# harp_expander.net
KiCad netlist of a schematic drawn in EAGLE
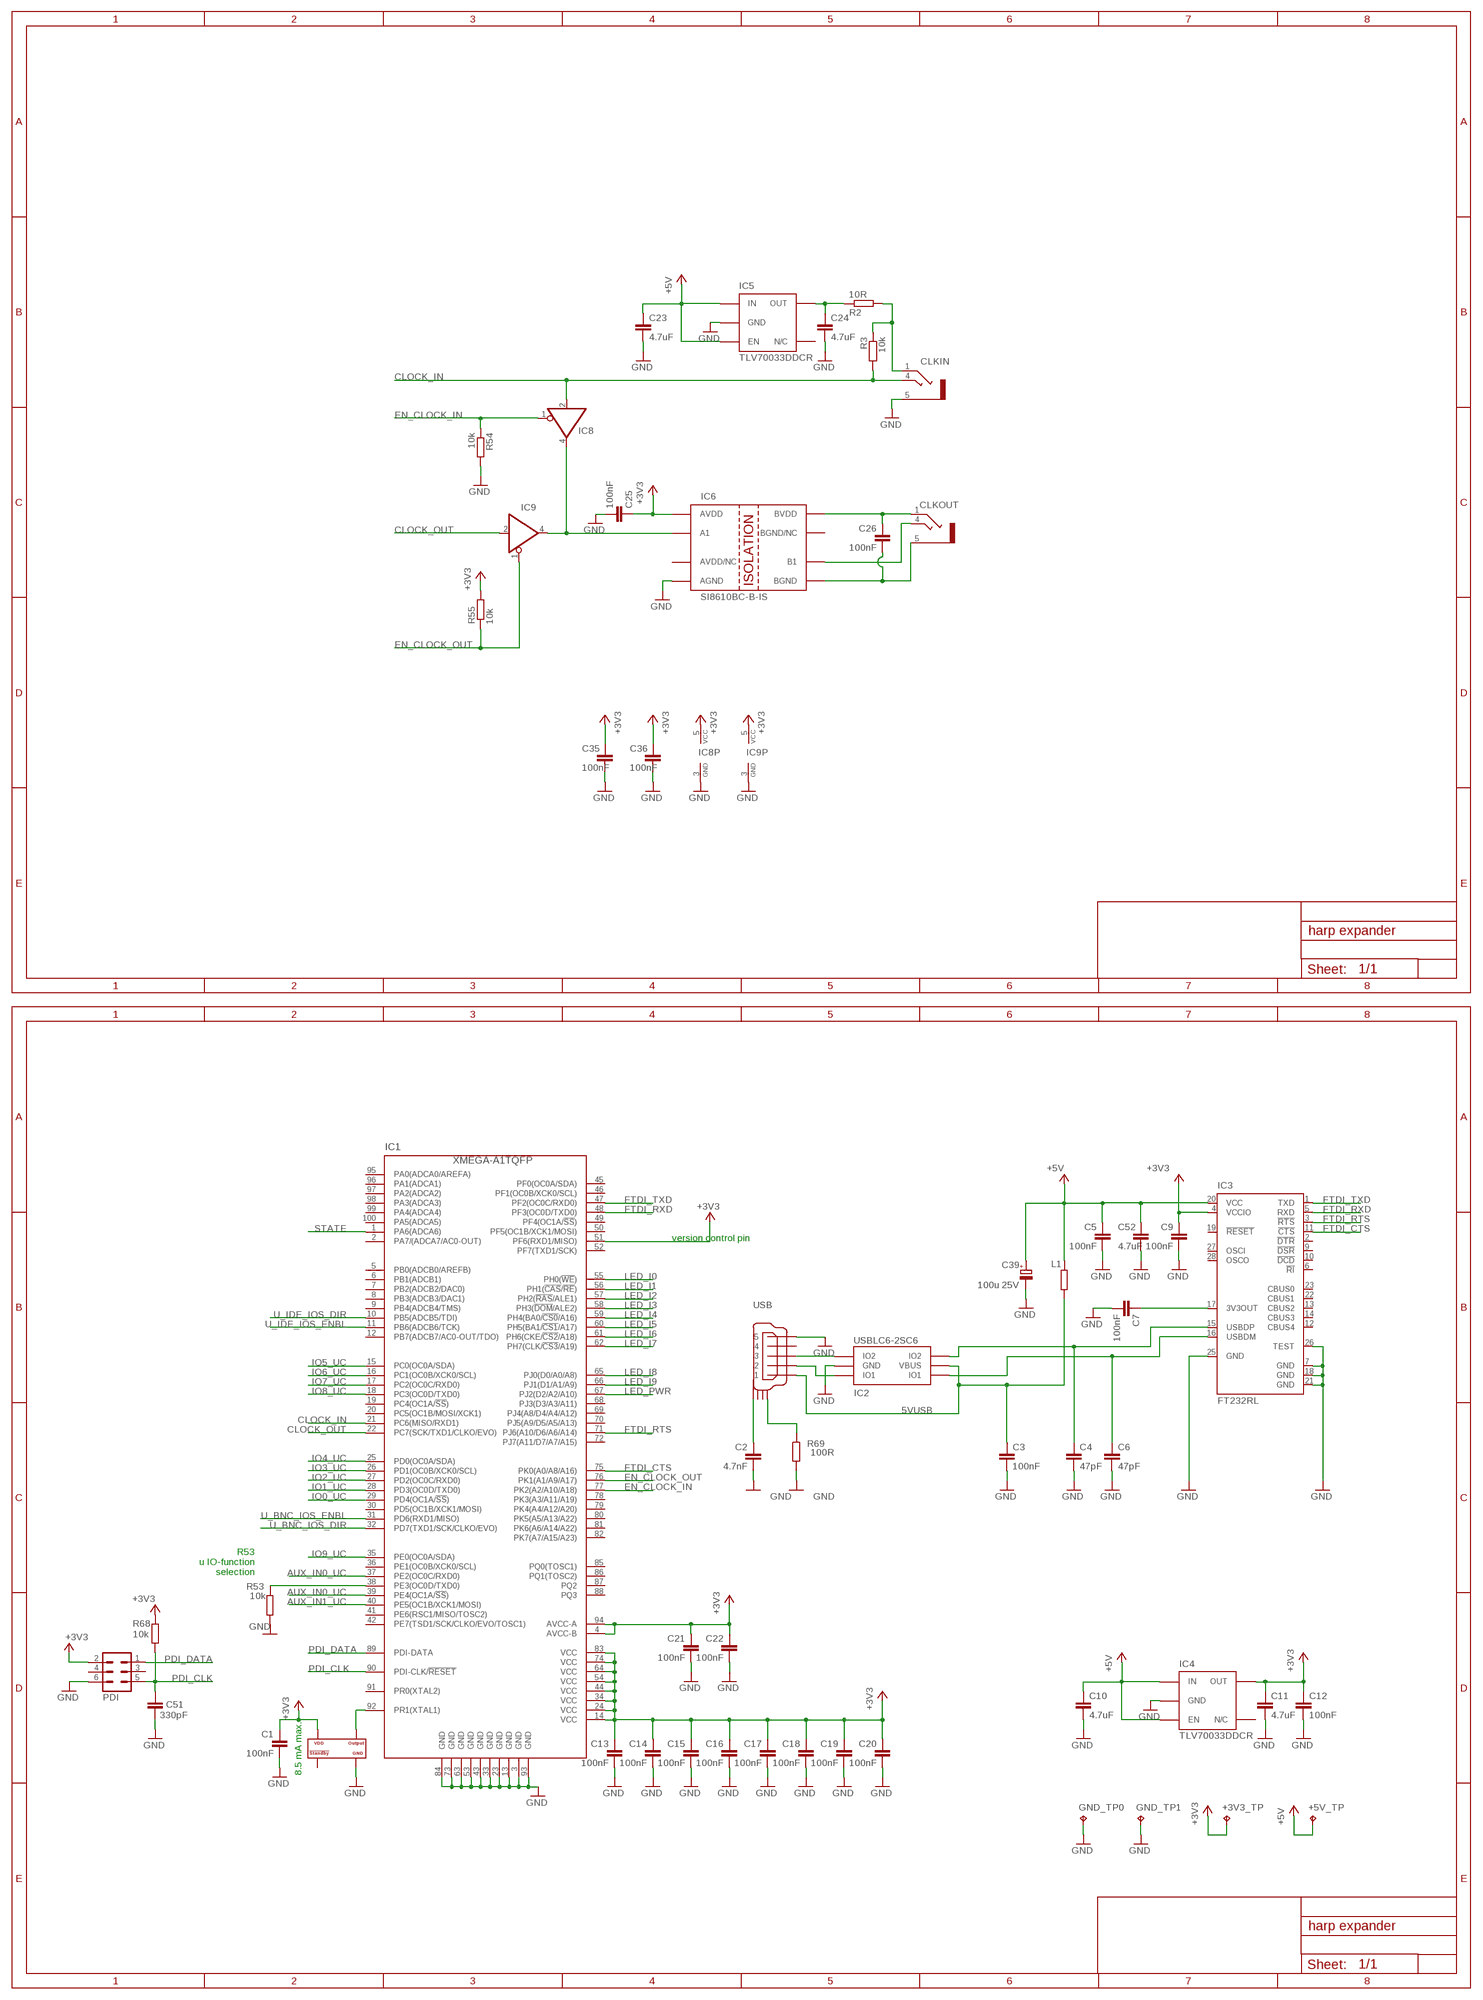
[diagram p0: schematic, sheet 1, part 1 of 2]
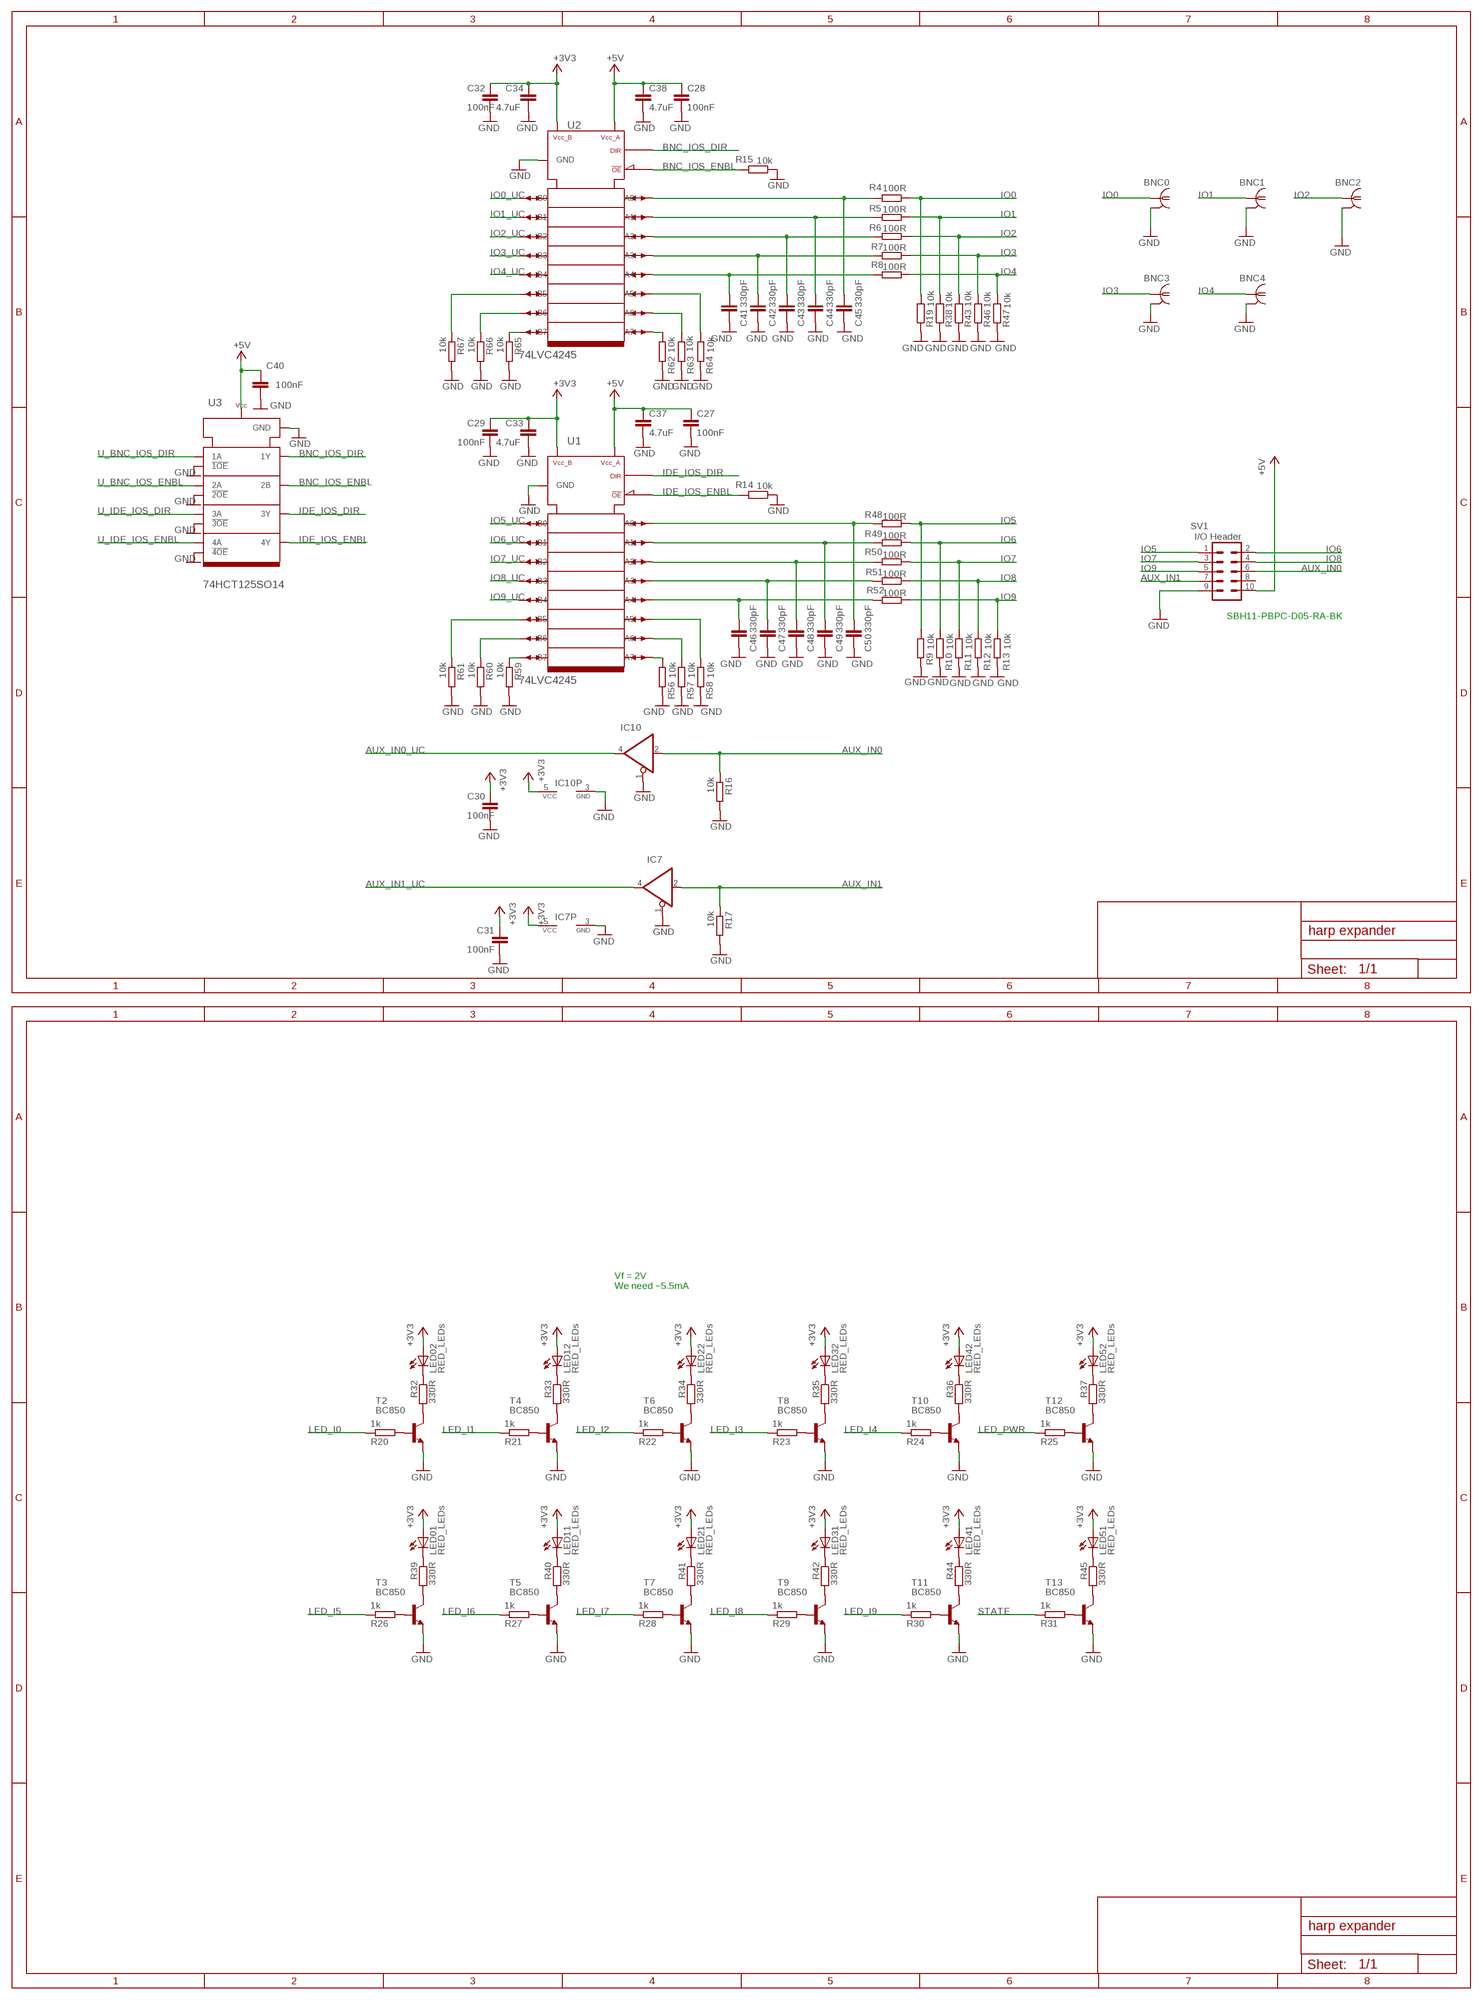
[diagram p1: schematic, sheet 1, part 2 of 2]

(export (version "E")
  (design (tool "Eeschema 10.0.6"))
  (components
    (comp (ref "+3V3_TP")
      (value "TPPAD1-13")
      (footprint "eagle-import:P1-13")
      (fields (field (name "MPN") "n.a."))
      (libsource (lib "eagle-import") (part "TPPAD1-13"))
    )
    (comp (ref "+5V_TP")
      (value "TPPAD1-13")
      (footprint "eagle-import:P1-13")
      (fields (field (name "MPN") "n.a."))
      (libsource (lib "eagle-import") (part "TPPAD1-13"))
    )
    (comp (ref "BNC0")
      (value "BNC plug")
      (footprint "eagle-import:0731000105")
      (fields (field (name "MPN") "73100-0105"))
      (libsource (lib "eagle-import") (part "BNC_0731000105"))
    )
    (comp (ref "BNC1")
      (value "BNC plug")
      (footprint "eagle-import:0731000105")
      (fields (field (name "MPN") "73100-0105"))
      (libsource (lib "eagle-import") (part "BNC_0731000105"))
    )
    (comp (ref "BNC2")
      (value "BNC plug")
      (footprint "eagle-import:0731000105")
      (fields (field (name "MPN") "73100-0105"))
      (libsource (lib "eagle-import") (part "BNC_0731000105"))
    )
    (comp (ref "BNC3")
      (value "BNC plug")
      (footprint "eagle-import:0731000105")
      (fields (field (name "MPN") "73100-0105"))
      (libsource (lib "eagle-import") (part "BNC_0731000105"))
    )
    (comp (ref "BNC4")
      (value "BNC plug")
      (footprint "eagle-import:0731000105")
      (fields (field (name "MPN") "73100-0105"))
      (libsource (lib "eagle-import") (part "BNC_0731000105"))
    )
    (comp (ref "C1")
      (value "100nF")
      (footprint "eagle-import:C0402")
      (fields (field (name "MPN") "MC0402B104K160CT"))
      (libsource (lib "eagle-import") (part "C-EUC0402"))
    )
    (comp (ref "C2")
      (value "4.7nF")
      (footprint "eagle-import:C0402")
      (fields (field (name "MPN") "885012205084"))
      (libsource (lib "eagle-import") (part "C-EUC0402"))
    )
    (comp (ref "C3")
      (value "100nF")
      (footprint "eagle-import:C0402")
      (fields (field (name "MPN") "MC0402B104K160CT"))
      (libsource (lib "eagle-import") (part "C-EUC0402"))
    )
    (comp (ref "C4")
      (value "47pF")
      (footprint "eagle-import:C0402")
      (fields (field (name "MPN") "04025A470JAT2A"))
      (libsource (lib "eagle-import") (part "C-EUC0402"))
    )
    (comp (ref "C5")
      (value "100nF")
      (footprint "eagle-import:C0402")
      (fields (field (name "MPN") "MC0402B104K160CT"))
      (libsource (lib "eagle-import") (part "C-EUC0402"))
    )
    (comp (ref "C6")
      (value "47pF")
      (footprint "eagle-import:C0402")
      (fields (field (name "MPN") "04025A470JAT2A"))
      (libsource (lib "eagle-import") (part "C-EUC0402"))
    )
    (comp (ref "C7")
      (value "100nF")
      (footprint "eagle-import:C0402")
      (fields (field (name "MPN") "MC0402B104K160CT"))
      (libsource (lib "eagle-import") (part "C-EUC0402"))
    )
    (comp (ref "C9")
      (value "100nF")
      (footprint "eagle-import:C0402")
      (fields (field (name "MPN") "MC0402B104K160CT"))
      (libsource (lib "eagle-import") (part "C-EUC0402"))
    )
    (comp (ref "C10")
      (value "4.7uF")
      (footprint "eagle-import:C0603")
      (fields (field (name "MPN") "C1608X6S1C475K080AC"))
      (libsource (lib "eagle-import") (part "C-EUC0603"))
    )
    (comp (ref "C11")
      (value "4.7uF")
      (footprint "eagle-import:C0603")
      (fields (field (name "MPN") "C1608X6S1C475K080AC"))
      (libsource (lib "eagle-import") (part "C-EUC0603"))
    )
    (comp (ref "C12")
      (value "100nF")
      (footprint "eagle-import:C0402")
      (fields (field (name "MPN") "MC0402B104K160CT"))
      (libsource (lib "eagle-import") (part "C-EUC0402"))
    )
    (comp (ref "C13")
      (value "100nF")
      (footprint "eagle-import:C0402")
      (fields (field (name "MPN") "MC0402B104K160CT"))
      (libsource (lib "eagle-import") (part "C-EUC0402"))
    )
    (comp (ref "C14")
      (value "100nF")
      (footprint "eagle-import:C0402")
      (fields (field (name "MPN") "MC0402B104K160CT"))
      (libsource (lib "eagle-import") (part "C-EUC0402"))
    )
    (comp (ref "C15")
      (value "100nF")
      (footprint "eagle-import:C0402")
      (fields (field (name "MPN") "MC0402B104K160CT"))
      (libsource (lib "eagle-import") (part "C-EUC0402"))
    )
    (comp (ref "C16")
      (value "100nF")
      (footprint "eagle-import:C0402")
      (fields (field (name "MPN") "MC0402B104K160CT"))
      (libsource (lib "eagle-import") (part "C-EUC0402"))
    )
    (comp (ref "C17")
      (value "100nF")
      (footprint "eagle-import:C0402")
      (fields (field (name "MPN") "MC0402B104K160CT"))
      (libsource (lib "eagle-import") (part "C-EUC0402"))
    )
    (comp (ref "C18")
      (value "100nF")
      (footprint "eagle-import:C0402")
      (fields (field (name "MPN") "MC0402B104K160CT"))
      (libsource (lib "eagle-import") (part "C-EUC0402"))
    )
    (comp (ref "C19")
      (value "100nF")
      (footprint "eagle-import:C0402")
      (fields (field (name "MPN") "MC0402B104K160CT"))
      (libsource (lib "eagle-import") (part "C-EUC0402"))
    )
    (comp (ref "C20")
      (value "100nF")
      (footprint "eagle-import:C0402")
      (fields (field (name "MPN") "MC0402B104K160CT"))
      (libsource (lib "eagle-import") (part "C-EUC0402"))
    )
    (comp (ref "C21")
      (value "100nF")
      (footprint "eagle-import:C0402")
      (fields (field (name "MPN") "MC0402B104K160CT"))
      (libsource (lib "eagle-import") (part "C-EUC0402"))
    )
    (comp (ref "C22")
      (value "100nF")
      (footprint "eagle-import:C0402")
      (fields (field (name "MPN") "MC0402B104K160CT"))
      (libsource (lib "eagle-import") (part "C-EUC0402"))
    )
    (comp (ref "C23")
      (value "4.7uF")
      (footprint "eagle-import:C0603")
      (fields (field (name "MPN") "C1608X6S1C475K080AC"))
      (libsource (lib "eagle-import") (part "C-EUC0603"))
    )
    (comp (ref "C24")
      (value "4.7uF")
      (footprint "eagle-import:C0603")
      (fields (field (name "MPN") "C1608X6S1C475K080AC"))
      (libsource (lib "eagle-import") (part "C-EUC0603"))
    )
    (comp (ref "C25")
      (value "100nF")
      (footprint "eagle-import:C0402")
      (fields (field (name "MPN") "MC0402B104K160CT"))
      (libsource (lib "eagle-import") (part "C-EUC0402"))
    )
    (comp (ref "C26")
      (value "100nF")
      (footprint "eagle-import:C0402")
      (fields (field (name "MPN") "MC0402B104K160CT"))
      (libsource (lib "eagle-import") (part "C-EUC0402"))
    )
    (comp (ref "C27")
      (value "100nF")
      (footprint "eagle-import:C0402")
      (fields (field (name "MPN") "MC0402B104K160CT"))
      (libsource (lib "eagle-import") (part "C-EUC0402"))
    )
    (comp (ref "C28")
      (value "100nF")
      (footprint "eagle-import:C0402")
      (fields (field (name "MPN") "MC0402B104K160CT"))
      (libsource (lib "eagle-import") (part "C-EUC0402"))
    )
    (comp (ref "C29")
      (value "100nF")
      (footprint "eagle-import:C0402")
      (fields (field (name "MPN") "MC0402B104K160CT"))
      (libsource (lib "eagle-import") (part "C-EUC0402"))
    )
    (comp (ref "C30")
      (value "100nF")
      (footprint "eagle-import:C0402")
      (fields (field (name "MPN") "MC0402B104K160CT"))
      (libsource (lib "eagle-import") (part "C-EUC0402"))
    )
    (comp (ref "C31")
      (value "100nF")
      (footprint "eagle-import:C0402")
      (fields (field (name "MPN") "MC0402B104K160CT"))
      (libsource (lib "eagle-import") (part "C-EUC0402"))
    )
    (comp (ref "C32")
      (value "100nF")
      (footprint "eagle-import:C0402")
      (fields (field (name "MPN") "MC0402B104K160CT"))
      (libsource (lib "eagle-import") (part "C-EUC0402"))
    )
    (comp (ref "C33")
      (value "4.7uF")
      (footprint "eagle-import:C0603")
      (fields (field (name "MPN") "C1608X6S1C475K080AC"))
      (libsource (lib "eagle-import") (part "C-EUC0603"))
    )
    (comp (ref "C34")
      (value "4.7uF")
      (footprint "eagle-import:C0603")
      (fields (field (name "MPN") "C1608X6S1C475K080AC"))
      (libsource (lib "eagle-import") (part "C-EUC0603"))
    )
    (comp (ref "C35")
      (value "100nF")
      (footprint "eagle-import:C0402")
      (fields (field (name "MPN") "MC0402B104K160CT"))
      (libsource (lib "eagle-import") (part "C-EUC0402"))
    )
    (comp (ref "C36")
      (value "100nF")
      (footprint "eagle-import:C0402")
      (fields (field (name "MPN") "MC0402B104K160CT"))
      (libsource (lib "eagle-import") (part "C-EUC0402"))
    )
    (comp (ref "C37")
      (value "4.7uF")
      (footprint "eagle-import:C0603")
      (fields (field (name "MPN") "C1608X6S1C475K080AC"))
      (libsource (lib "eagle-import") (part "C-EUC0603"))
    )
    (comp (ref "C38")
      (value "4.7uF")
      (footprint "eagle-import:C0603")
      (fields (field (name "MPN") "C1608X6S1C475K080AC"))
      (libsource (lib "eagle-import") (part "C-EUC0603"))
    )
    (comp (ref "C39")
      (value "100u 25V")
      (footprint "eagle-import:TT2D6")
      (fields (field (name "MPN") "EEUFM1E101B"))
      (libsource (lib "eagle-import") (part "CPOL-EUTT2D6"))
    )
    (comp (ref "C40")
      (value "100nF")
      (footprint "eagle-import:C0402")
      (fields (field (name "MPN") "MC0402B104K160CT"))
      (libsource (lib "eagle-import") (part "C-EUC0402"))
    )
    (comp (ref "C41")
      (value "330pF")
      (footprint "eagle-import:C0402")
      (fields (field (name "MPN") "C0402C331J5GACTU"))
      (libsource (lib "eagle-import") (part "C-EUC0402"))
    )
    (comp (ref "C42")
      (value "330pF")
      (footprint "eagle-import:C0402")
      (fields (field (name "MPN") "C0402C331J5GACTU"))
      (libsource (lib "eagle-import") (part "C-EUC0402"))
    )
    (comp (ref "C43")
      (value "330pF")
      (footprint "eagle-import:C0402")
      (fields (field (name "MPN") "C0402C331J5GACTU"))
      (libsource (lib "eagle-import") (part "C-EUC0402"))
    )
    (comp (ref "C44")
      (value "330pF")
      (footprint "eagle-import:C0402")
      (fields (field (name "MPN") "C0402C331J5GACTU"))
      (libsource (lib "eagle-import") (part "C-EUC0402"))
    )
    (comp (ref "C45")
      (value "330pF")
      (footprint "eagle-import:C0402")
      (fields (field (name "MPN") "C0402C331J5GACTU"))
      (libsource (lib "eagle-import") (part "C-EUC0402"))
    )
    (comp (ref "C46")
      (value "330pF")
      (footprint "eagle-import:C0402")
      (fields (field (name "MPN") "C0402C331J5GACTU"))
      (libsource (lib "eagle-import") (part "C-EUC0402"))
    )
    (comp (ref "C47")
      (value "330pF")
      (footprint "eagle-import:C0402")
      (fields (field (name "MPN") "C0402C331J5GACTU"))
      (libsource (lib "eagle-import") (part "C-EUC0402"))
    )
    (comp (ref "C48")
      (value "330pF")
      (footprint "eagle-import:C0402")
      (fields (field (name "MPN") "C0402C331J5GACTU"))
      (libsource (lib "eagle-import") (part "C-EUC0402"))
    )
    (comp (ref "C49")
      (value "330pF")
      (footprint "eagle-import:C0402")
      (fields (field (name "MPN") "C0402C331J5GACTU"))
      (libsource (lib "eagle-import") (part "C-EUC0402"))
    )
    (comp (ref "C50")
      (value "330pF")
      (footprint "eagle-import:C0402")
      (fields (field (name "MPN") "C0402C331J5GACTU"))
      (libsource (lib "eagle-import") (part "C-EUC0402"))
    )
    (comp (ref "C51")
      (value "330pF")
      (footprint "eagle-import:C0402")
      (fields (field (name "MPN") "C0402C331J5GACTU"))
      (libsource (lib "eagle-import") (part "C-EUC0402"))
    )
    (comp (ref "C52")
      (value "4.7uF")
      (footprint "eagle-import:C0603")
      (fields (field (name "MPN") "C1608X6S1C475K080AC"))
      (libsource (lib "eagle-import") (part "C-EUC0603"))
    )
    (comp (ref "CLKIN")
      (value "CLCK_JACK")
      (footprint "eagle-import:35RASMT2BHNTRX")
      (fields (field (name "MPN") "35RASMT2BHNTRX"))
      (libsource (lib "eagle-import") (part "STEREO_JACK"))
    )
    (comp (ref "CLKOUT")
      (value "CLCK_JACK")
      (footprint "eagle-import:35RASMT2BHNTRX")
      (fields (field (name "MPN") "35RASMT2BHNTRX"))
      (libsource (lib "eagle-import") (part "STEREO_JACK"))
    )
    (comp (ref "GND_TP0")
      (value "TPPAD1-13")
      (footprint "eagle-import:P1-13")
      (fields (field (name "MPN") "n.a."))
      (libsource (lib "eagle-import") (part "TPPAD1-13"))
    )
    (comp (ref "GND_TP1")
      (value "TPPAD1-13")
      (footprint "eagle-import:P1-13")
      (fields (field (name "MPN") "n.a."))
      (libsource (lib "eagle-import") (part "TPPAD1-13"))
    )
    (comp (ref "IC1")
      (value "XMEGA-A1TQFP")
      (footprint "eagle-import:TQFP100")
      (fields (field (name "MPN") "ATXMEGA128A1U-AU"))
      (libsource (lib "eagle-import") (part "XMEGA-A1TQFP"))
    )
    (comp (ref "IC2")
      (value "USBLC6-2SC6")
      (footprint "eagle-import:SOT23-6L")
      (libsource (lib "eagle-import") (part "USBLC6-2"))
    )
    (comp (ref "IC3")
      (value "FT232RL")
      (footprint "eagle-import:SSOP28")
      (fields (field (name "MPN") "FT232RL-REEL"))
      (libsource (lib "eagle-import") (part "FT232RL"))
    )
    (comp (ref "IC4")
      (value "TLV70033DDCR")
      (footprint "eagle-import:TSOT23-5")
      (libsource (lib "eagle-import") (part "TLV700XX"))
    )
    (comp (ref "IC5")
      (value "TLV70033DDCR")
      (footprint "eagle-import:TSOT23-5")
      (libsource (lib "eagle-import") (part "harp input expander_TLV700XX"))
    )
    (comp (ref "IC6")
      (value "SI8610BC-B-IS")
      (footprint "eagle-import:SO-08")
      (fields (field (name "MPN") "SI8610EC-B-IS"))
      (libsource (lib "eagle-import") (part "SI8610"))
    )
    (comp (ref "IC7")
      (value "SN74LVC1G125DBVT")
      (footprint "eagle-import:SOT23-5")
      (fields (field (name "MPN") "SN74LVC1G125DBVT"))
      (libsource (lib "eagle-import") (part "741G125DBVAHC"))
    )
    (comp (ref "IC8")
      (value "SN74LVC1G125DBVT")
      (footprint "eagle-import:SOT23-5")
      (fields (field (name "MPN") "SN74LVC1G125DBVT"))
      (libsource (lib "eagle-import") (part "741G125DBVAHC"))
    )
    (comp (ref "IC9")
      (value "SN74LVC1G125DBVT")
      (footprint "eagle-import:SOT23-5")
      (fields (field (name "MPN") "SN74LVC1G125DBVT"))
      (libsource (lib "eagle-import") (part "741G125DBVAHC"))
    )
    (comp (ref "IC10")
      (value "SN74LVC1G125DBVT")
      (footprint "eagle-import:SOT23-5")
      (fields (field (name "MPN") "SN74LVC1G125DBVT"))
      (libsource (lib "eagle-import") (part "741G125DBVAHC"))
    )
    (comp (ref "L1")
      (value "40R@100MHz")
      (footprint "eagle-import:R0805")
      (fields (field (name "MPN") "MI0805K400R-10"))
      (libsource (lib "eagle-import") (part "R-EU_R0805"))
    )
    (comp (ref "LED0")
      (value "RED_LEDs")
      (footprint "eagle-import:569-011X-X00_LED_ARRAY")
      (fields (field (name "MPN") "5690-111-100F"))
      (libsource (lib "eagle-import") (part "LED_2X_VERTICAL"))
    )
    (comp (ref "LED1")
      (value "RED_LEDs")
      (footprint "eagle-import:569-011X-X00_LED_ARRAY")
      (fields (field (name "MPN") "5690-111-100F"))
      (libsource (lib "eagle-import") (part "LED_2X_VERTICAL"))
    )
    (comp (ref "LED2")
      (value "RED_LEDs")
      (footprint "eagle-import:569-011X-X00_LED_ARRAY")
      (fields (field (name "MPN") "5690-111-100F"))
      (libsource (lib "eagle-import") (part "LED_2X_VERTICAL"))
    )
    (comp (ref "LED3")
      (value "RED_LEDs")
      (footprint "eagle-import:569-011X-X00_LED_ARRAY")
      (fields (field (name "MPN") "5690-111-100F"))
      (libsource (lib "eagle-import") (part "LED_2X_VERTICAL"))
    )
    (comp (ref "LED4")
      (value "RED_LEDs")
      (footprint "eagle-import:569-011X-X00_LED_ARRAY")
      (fields (field (name "MPN") "5690-111-100F"))
      (libsource (lib "eagle-import") (part "LED_2X_VERTICAL"))
    )
    (comp (ref "LED5")
      (value "RED_LEDs")
      (footprint "eagle-import:569-011X-X00_LED_ARRAY")
      (fields (field (name "MPN") "5690-111-100F"))
      (libsource (lib "eagle-import") (part "LED_2X_VERTICAL"))
    )
    (comp (ref "OSC")
      (value "Oscillator")
      (footprint "eagle-import:OSCILLATOR_3.2X2.5")
      (fields (field (name "MPN") "O 32,0-JT32C-A-K-3,3-LF"))
      (libsource (lib "eagle-import") (part "OSCILLATOR"))
    )
    (comp (ref "PDI")
      (value "PROG HEADER")
      (footprint "eagle-import:MA03-2")
      (fields (field (name "MPN") "67996-206HLF"))
      (libsource (lib "eagle-import") (part "MA03-2"))
    )
    (comp (ref "R2")
      (value "10R")
      (footprint "eagle-import:R0402")
      (fields (field (name "MPN") "CRCW040210R0FKEDHP"))
      (libsource (lib "eagle-import") (part "R-EU_R0402"))
    )
    (comp (ref "R3")
      (value "10k")
      (footprint "eagle-import:R0402")
      (fields (field (name "MPN") "CRCW040210K0FKED"))
      (libsource (lib "eagle-import") (part "R-EU_R0402"))
    )
    (comp (ref "R4")
      (value "100R")
      (footprint "eagle-import:R0603")
      (fields (field (name "MPN") "CRCW0603100RFKEAHP"))
      (libsource (lib "eagle-import") (part "R-EU_R0603"))
    )
    (comp (ref "R5")
      (value "100R")
      (footprint "eagle-import:R0603")
      (fields (field (name "MPN") "CRCW0603100RFKEAHP"))
      (libsource (lib "eagle-import") (part "R-EU_R0603"))
    )
    (comp (ref "R6")
      (value "100R")
      (footprint "eagle-import:R0603")
      (fields (field (name "MPN") "CRCW0603100RFKEAHP"))
      (libsource (lib "eagle-import") (part "R-EU_R0603"))
    )
    (comp (ref "R7")
      (value "100R")
      (footprint "eagle-import:R0603")
      (fields (field (name "MPN") "CRCW0603100RFKEAHP"))
      (libsource (lib "eagle-import") (part "R-EU_R0603"))
    )
    (comp (ref "R8")
      (value "100R")
      (footprint "eagle-import:R0603")
      (fields (field (name "MPN") "CRCW0603100RFKEAHP"))
      (libsource (lib "eagle-import") (part "R-EU_R0603"))
    )
    (comp (ref "R9")
      (value "10k")
      (footprint "eagle-import:R0402")
      (fields (field (name "MPN") "CRCW040210K0FKED"))
      (libsource (lib "eagle-import") (part "R-EU_R0402"))
    )
    (comp (ref "R10")
      (value "10k")
      (footprint "eagle-import:R0402")
      (fields (field (name "MPN") "CRCW040210K0FKED"))
      (libsource (lib "eagle-import") (part "R-EU_R0402"))
    )
    (comp (ref "R11")
      (value "10k")
      (footprint "eagle-import:R0402")
      (fields (field (name "MPN") "CRCW040210K0FKED"))
      (libsource (lib "eagle-import") (part "R-EU_R0402"))
    )
    (comp (ref "R12")
      (value "10k")
      (footprint "eagle-import:R0402")
      (fields (field (name "MPN") "CRCW040210K0FKED"))
      (libsource (lib "eagle-import") (part "R-EU_R0402"))
    )
    (comp (ref "R13")
      (value "10k")
      (footprint "eagle-import:R0402")
      (fields (field (name "MPN") "CRCW040210K0FKED"))
      (libsource (lib "eagle-import") (part "R-EU_R0402"))
    )
    (comp (ref "R14")
      (value "10k")
      (footprint "eagle-import:R0402")
      (fields (field (name "MPN") "CRCW040210K0FKED"))
      (libsource (lib "eagle-import") (part "R-EU_R0402"))
    )
    (comp (ref "R15")
      (value "10k")
      (footprint "eagle-import:R0402")
      (fields (field (name "MPN") "CRCW040210K0FKED"))
      (libsource (lib "eagle-import") (part "R-EU_R0402"))
    )
    (comp (ref "R16")
      (value "10k")
      (footprint "eagle-import:R0402")
      (fields (field (name "MPN") "CRCW040210K0FKED"))
      (libsource (lib "eagle-import") (part "R-EU_R0402"))
    )
    (comp (ref "R17")
      (value "10k")
      (footprint "eagle-import:R0402")
      (fields (field (name "MPN") "CRCW040210K0FKED"))
      (libsource (lib "eagle-import") (part "R-EU_R0402"))
    )
    (comp (ref "R19")
      (value "10k")
      (footprint "eagle-import:R0402")
      (fields (field (name "MPN") "CRCW040210K0FKED"))
      (libsource (lib "eagle-import") (part "R-EU_R0402"))
    )
    (comp (ref "R20")
      (value "1k")
      (footprint "eagle-import:R0402")
      (fields (field (name "MPN") "CRCW04021K00FKED"))
      (libsource (lib "eagle-import") (part "R-EU_R0402"))
    )
    (comp (ref "R21")
      (value "1k")
      (footprint "eagle-import:R0402")
      (fields (field (name "MPN") "CRCW04021K00FKED"))
      (libsource (lib "eagle-import") (part "R-EU_R0402"))
    )
    (comp (ref "R22")
      (value "1k")
      (footprint "eagle-import:R0402")
      (fields (field (name "MPN") "CRCW04021K00FKED"))
      (libsource (lib "eagle-import") (part "R-EU_R0402"))
    )
    (comp (ref "R23")
      (value "1k")
      (footprint "eagle-import:R0402")
      (fields (field (name "MPN") "CRCW04021K00FKED"))
      (libsource (lib "eagle-import") (part "R-EU_R0402"))
    )
    (comp (ref "R24")
      (value "1k")
      (footprint "eagle-import:R0402")
      (fields (field (name "MPN") "CRCW04021K00FKED"))
      (libsource (lib "eagle-import") (part "R-EU_R0402"))
    )
    (comp (ref "R25")
      (value "1k")
      (footprint "eagle-import:R0402")
      (fields (field (name "MPN") "CRCW04021K00FKED"))
      (libsource (lib "eagle-import") (part "R-EU_R0402"))
    )
    (comp (ref "R26")
      (value "1k")
      (footprint "eagle-import:R0402")
      (fields (field (name "MPN") "CRCW04021K00FKED"))
      (libsource (lib "eagle-import") (part "R-EU_R0402"))
    )
    (comp (ref "R27")
      (value "1k")
      (footprint "eagle-import:R0402")
      (fields (field (name "MPN") "CRCW04021K00FKED"))
      (libsource (lib "eagle-import") (part "R-EU_R0402"))
    )
    (comp (ref "R28")
      (value "1k")
      (footprint "eagle-import:R0402")
      (fields (field (name "MPN") "CRCW04021K00FKED"))
      (libsource (lib "eagle-import") (part "R-EU_R0402"))
    )
    (comp (ref "R29")
      (value "1k")
      (footprint "eagle-import:R0402")
      (fields (field (name "MPN") "CRCW04021K00FKED"))
      (libsource (lib "eagle-import") (part "R-EU_R0402"))
    )
    (comp (ref "R30")
      (value "1k")
      (footprint "eagle-import:R0402")
      (fields (field (name "MPN") "CRCW04021K00FKED"))
      (libsource (lib "eagle-import") (part "R-EU_R0402"))
    )
    (comp (ref "R31")
      (value "1k")
      (footprint "eagle-import:R0402")
      (fields (field (name "MPN") "CRCW04021K00FKED"))
      (libsource (lib "eagle-import") (part "R-EU_R0402"))
    )
    (comp (ref "R32")
      (value "330R")
      (footprint "eagle-import:R0402")
      (fields (field (name "MPN") "RC0402FR-07330RL "))
      (libsource (lib "eagle-import") (part "R-EU_R0402"))
    )
    (comp (ref "R33")
      (value "330R")
      (footprint "eagle-import:R0402")
      (fields (field (name "MPN") "RC0402FR-07330RL "))
      (libsource (lib "eagle-import") (part "R-EU_R0402"))
    )
    (comp (ref "R34")
      (value "330R")
      (footprint "eagle-import:R0402")
      (fields (field (name "MPN") "RC0402FR-07330RL "))
      (libsource (lib "eagle-import") (part "R-EU_R0402"))
    )
    (comp (ref "R35")
      (value "330R")
      (footprint "eagle-import:R0402")
      (fields (field (name "MPN") "RC0402FR-07330RL "))
      (libsource (lib "eagle-import") (part "R-EU_R0402"))
    )
    (comp (ref "R36")
      (value "330R")
      (footprint "eagle-import:R0402")
      (fields (field (name "MPN") "RC0402FR-07330RL "))
      (libsource (lib "eagle-import") (part "R-EU_R0402"))
    )
    (comp (ref "R37")
      (value "330R")
      (footprint "eagle-import:R0402")
      (fields (field (name "MPN") "RC0402FR-07330RL "))
      (libsource (lib "eagle-import") (part "R-EU_R0402"))
    )
    (comp (ref "R38")
      (value "10k")
      (footprint "eagle-import:R0402")
      (fields (field (name "MPN") "CRCW040210K0FKED"))
      (libsource (lib "eagle-import") (part "R-EU_R0402"))
    )
    (comp (ref "R39")
      (value "330R")
      (footprint "eagle-import:R0402")
      (fields (field (name "MPN") "RC0402FR-07330RL "))
      (libsource (lib "eagle-import") (part "R-EU_R0402"))
    )
    (comp (ref "R40")
      (value "330R")
      (footprint "eagle-import:R0402")
      (fields (field (name "MPN") "RC0402FR-07330RL "))
      (libsource (lib "eagle-import") (part "R-EU_R0402"))
    )
    (comp (ref "R41")
      (value "330R")
      (footprint "eagle-import:R0402")
      (fields (field (name "MPN") "RC0402FR-07330RL "))
      (libsource (lib "eagle-import") (part "R-EU_R0402"))
    )
    (comp (ref "R42")
      (value "330R")
      (footprint "eagle-import:R0402")
      (fields (field (name "MPN") "RC0402FR-07330RL "))
      (libsource (lib "eagle-import") (part "R-EU_R0402"))
    )
    (comp (ref "R43")
      (value "10k")
      (footprint "eagle-import:R0402")
      (fields (field (name "MPN") "CRCW040210K0FKED"))
      (libsource (lib "eagle-import") (part "R-EU_R0402"))
    )
    (comp (ref "R44")
      (value "330R")
      (footprint "eagle-import:R0402")
      (fields (field (name "MPN") "RC0402FR-07330RL "))
      (libsource (lib "eagle-import") (part "R-EU_R0402"))
    )
    (comp (ref "R45")
      (value "330R")
      (footprint "eagle-import:R0402")
      (fields (field (name "MPN") "RC0402FR-07330RL "))
      (libsource (lib "eagle-import") (part "R-EU_R0402"))
    )
    (comp (ref "R46")
      (value "10k")
      (footprint "eagle-import:R0402")
      (fields (field (name "MPN") "CRCW040210K0FKED"))
      (libsource (lib "eagle-import") (part "R-EU_R0402"))
    )
    (comp (ref "R47")
      (value "10k")
      (footprint "eagle-import:R0402")
      (fields (field (name "MPN") "CRCW040210K0FKED"))
      (libsource (lib "eagle-import") (part "R-EU_R0402"))
    )
    (comp (ref "R48")
      (value "100R")
      (footprint "eagle-import:R0603")
      (fields (field (name "MPN") "CRCW0603100RFKEAHP"))
      (libsource (lib "eagle-import") (part "R-EU_R0603"))
    )
    (comp (ref "R49")
      (value "100R")
      (footprint "eagle-import:R0603")
      (fields (field (name "MPN") "CRCW0603100RFKEAHP"))
      (libsource (lib "eagle-import") (part "R-EU_R0603"))
    )
    (comp (ref "R50")
      (value "100R")
      (footprint "eagle-import:R0603")
      (fields (field (name "MPN") "CRCW0603100RFKEAHP"))
      (libsource (lib "eagle-import") (part "R-EU_R0603"))
    )
    (comp (ref "R51")
      (value "100R")
      (footprint "eagle-import:R0603")
      (fields (field (name "MPN") "CRCW0603100RFKEAHP"))
      (libsource (lib "eagle-import") (part "R-EU_R0603"))
    )
    (comp (ref "R52")
      (value "100R")
      (footprint "eagle-import:R0603")
      (fields (field (name "MPN") "CRCW0603100RFKEAHP"))
      (libsource (lib "eagle-import") (part "R-EU_R0603"))
    )
    (comp (ref "R53")
      (value "10k")
      (footprint "eagle-import:R0402")
      (fields (field (name "MPN") "CRCW040210K0FKED"))
      (libsource (lib "eagle-import") (part "R-EU_R0402"))
    )
    (comp (ref "R54")
      (value "10k")
      (footprint "eagle-import:R0402")
      (fields (field (name "MPN") "CRCW040210K0FKED"))
      (libsource (lib "eagle-import") (part "R-EU_R0402"))
    )
    (comp (ref "R55")
      (value "10k")
      (footprint "eagle-import:R0402")
      (fields (field (name "MPN") "CRCW040210K0FKED"))
      (libsource (lib "eagle-import") (part "R-EU_R0402"))
    )
    (comp (ref "R56")
      (value "10k")
      (footprint "eagle-import:R0402")
      (fields (field (name "MPN") "CRCW040210K0FKED"))
      (libsource (lib "eagle-import") (part "R-EU_R0402"))
    )
    (comp (ref "R57")
      (value "10k")
      (footprint "eagle-import:R0402")
      (fields (field (name "MPN") "CRCW040210K0FKED"))
      (libsource (lib "eagle-import") (part "R-EU_R0402"))
    )
    (comp (ref "R58")
      (value "10k")
      (footprint "eagle-import:R0402")
      (fields (field (name "MPN") "CRCW040210K0FKED"))
      (libsource (lib "eagle-import") (part "R-EU_R0402"))
    )
    (comp (ref "R59")
      (value "10k")
      (footprint "eagle-import:R0402")
      (fields (field (name "MPN") "CRCW040210K0FKED"))
      (libsource (lib "eagle-import") (part "R-EU_R0402"))
    )
    (comp (ref "R60")
      (value "10k")
      (footprint "eagle-import:R0402")
      (fields (field (name "MPN") "CRCW040210K0FKED"))
      (libsource (lib "eagle-import") (part "R-EU_R0402"))
    )
    (comp (ref "R61")
      (value "10k")
      (footprint "eagle-import:R0402")
      (fields (field (name "MPN") "CRCW040210K0FKED"))
      (libsource (lib "eagle-import") (part "R-EU_R0402"))
    )
    (comp (ref "R62")
      (value "10k")
      (footprint "eagle-import:R0402")
      (fields (field (name "MPN") "CRCW040210K0FKED"))
      (libsource (lib "eagle-import") (part "R-EU_R0402"))
    )
    (comp (ref "R63")
      (value "10k")
      (footprint "eagle-import:R0402")
      (fields (field (name "MPN") "CRCW040210K0FKED"))
      (libsource (lib "eagle-import") (part "R-EU_R0402"))
    )
    (comp (ref "R64")
      (value "10k")
      (footprint "eagle-import:R0402")
      (fields (field (name "MPN") "CRCW040210K0FKED"))
      (libsource (lib "eagle-import") (part "R-EU_R0402"))
    )
    (comp (ref "R65")
      (value "10k")
      (footprint "eagle-import:R0402")
      (fields (field (name "MPN") "CRCW040210K0FKED"))
      (libsource (lib "eagle-import") (part "R-EU_R0402"))
    )
    (comp (ref "R66")
      (value "10k")
      (footprint "eagle-import:R0402")
      (fields (field (name "MPN") "CRCW040210K0FKED"))
      (libsource (lib "eagle-import") (part "R-EU_R0402"))
    )
    (comp (ref "R67")
      (value "10k")
      (footprint "eagle-import:R0402")
      (fields (field (name "MPN") "CRCW040210K0FKED"))
      (libsource (lib "eagle-import") (part "R-EU_R0402"))
    )
    (comp (ref "R68")
      (value "10k")
      (footprint "eagle-import:R0402")
      (fields (field (name "MPN") "CRCW040210K0FKED"))
      (libsource (lib "eagle-import") (part "R-EU_R0402"))
    )
    (comp (ref "R69")
      (value "100R")
      (footprint "eagle-import:R0603")
      (fields (field (name "MPN") "CRCW0603100RFKEAHP"))
      (libsource (lib "eagle-import") (part "R-EU_R0603"))
    )
    (comp (ref "SV1")
      (value "I/O Header")
      (footprint "eagle-import:ML10L")
      (fields (field (name "MPN") "SBH11-PBPC-D05-RA-BK"))
      (libsource (lib "eagle-import") (part "ML10L"))
    )
    (comp (ref "T2")
      (value "BC850")
      (footprint "eagle-import:SOT23")
      (fields (field (name "MPN") "BC850C,215"))
      (libsource (lib "eagle-import") (part "BC850"))
    )
    (comp (ref "T3")
      (value "BC850")
      (footprint "eagle-import:SOT23")
      (fields (field (name "MPN") "BC850C,215"))
      (libsource (lib "eagle-import") (part "BC850"))
    )
    (comp (ref "T4")
      (value "BC850")
      (footprint "eagle-import:SOT23")
      (fields (field (name "MPN") "BC850C,215"))
      (libsource (lib "eagle-import") (part "BC850"))
    )
    (comp (ref "T5")
      (value "BC850")
      (footprint "eagle-import:SOT23")
      (fields (field (name "MPN") "BC850C,215"))
      (libsource (lib "eagle-import") (part "BC850"))
    )
    (comp (ref "T6")
      (value "BC850")
      (footprint "eagle-import:SOT23")
      (fields (field (name "MPN") "BC850C,215"))
      (libsource (lib "eagle-import") (part "BC850"))
    )
    (comp (ref "T7")
      (value "BC850")
      (footprint "eagle-import:SOT23")
      (fields (field (name "MPN") "BC850C,215"))
      (libsource (lib "eagle-import") (part "BC850"))
    )
    (comp (ref "T8")
      (value "BC850")
      (footprint "eagle-import:SOT23")
      (fields (field (name "MPN") "BC850C,215"))
      (libsource (lib "eagle-import") (part "BC850"))
    )
    (comp (ref "T9")
      (value "BC850")
      (footprint "eagle-import:SOT23")
      (fields (field (name "MPN") "BC850C,215"))
      (libsource (lib "eagle-import") (part "BC850"))
    )
    (comp (ref "T10")
      (value "BC850")
      (footprint "eagle-import:SOT23")
      (fields (field (name "MPN") "BC850C,215"))
      (libsource (lib "eagle-import") (part "BC850"))
    )
    (comp (ref "T11")
      (value "BC850")
      (footprint "eagle-import:SOT23")
      (fields (field (name "MPN") "BC850C,215"))
      (libsource (lib "eagle-import") (part "BC850"))
    )
    (comp (ref "T12")
      (value "BC850")
      (footprint "eagle-import:SOT23")
      (fields (field (name "MPN") "BC850C,215"))
      (libsource (lib "eagle-import") (part "BC850"))
    )
    (comp (ref "T13")
      (value "BC850")
      (footprint "eagle-import:SOT23")
      (fields (field (name "MPN") "BC850C,215"))
      (libsource (lib "eagle-import") (part "BC850"))
    )
    (comp (ref "U1")
      (value "744245X")
      (footprint "eagle-import:SO24L")
      (fields (field (name "MPN") "74LVC4245AD,118 "))
      (libsource (lib "eagle-import") (part "744245X"))
    )
    (comp (ref "U2")
      (value "744245X")
      (footprint "eagle-import:SO24L")
      (fields (field (name "MPN") "74LVC4245AD,118 "))
      (libsource (lib "eagle-import") (part "744245X"))
    )
    (comp (ref "U3")
      (value "74HCT125SO14")
      (footprint "eagle-import:SO14")
      (fields (field (name "MPN") "74HCT125D,653"))
      (libsource (lib "eagle-import") (part "74HCT125SO14"))
    )
    (comp (ref "USB")
      (value "mini USB")
      (footprint "eagle-import:240-0002-1")
      (fields (field (name "MPN") "UX60-MB-5S8 "))
      (libsource (lib "eagle-import") (part "USB_MINI_B"))
    )
  )
  (nets
    (net (code "1") (name "+3V3") (class "Default")
      (node (ref "+3V3_TP") (pin "TP") (pinfunction "TP_TP") (pintype "input"))
      (node (ref "C1") (pin "1") (pinfunction "1_1") (pintype "passive"))
      (node (ref "C11") (pin "1") (pinfunction "1_1") (pintype "passive"))
      (node (ref "C12") (pin "1") (pinfunction "1_1") (pintype "passive"))
      (node (ref "C13") (pin "1") (pinfunction "1_1") (pintype "passive"))
      (node (ref "C14") (pin "1") (pinfunction "1_1") (pintype "passive"))
      (node (ref "C15") (pin "1") (pinfunction "1_1") (pintype "passive"))
      (node (ref "C16") (pin "1") (pinfunction "1_1") (pintype "passive"))
      (node (ref "C17") (pin "1") (pinfunction "1_1") (pintype "passive"))
      (node (ref "C18") (pin "1") (pinfunction "1_1") (pintype "passive"))
      (node (ref "C19") (pin "1") (pinfunction "1_1") (pintype "passive"))
      (node (ref "C20") (pin "1") (pinfunction "1_1") (pintype "passive"))
      (node (ref "C21") (pin "1") (pinfunction "1_1") (pintype "passive"))
      (node (ref "C22") (pin "1") (pinfunction "1_1") (pintype "passive"))
      (node (ref "C25") (pin "1") (pinfunction "1_1") (pintype "passive"))
      (node (ref "C29") (pin "1") (pinfunction "1_1") (pintype "passive"))
      (node (ref "C30") (pin "1") (pinfunction "1_1") (pintype "passive"))
      (node (ref "C31") (pin "1") (pinfunction "1_1") (pintype "passive"))
      (node (ref "C32") (pin "1") (pinfunction "1_1") (pintype "passive"))
      (node (ref "C33") (pin "1") (pinfunction "1_1") (pintype "passive"))
      (node (ref "C34") (pin "1") (pinfunction "1_1") (pintype "passive"))
      (node (ref "C35") (pin "1") (pinfunction "1_1") (pintype "passive"))
      (node (ref "C36") (pin "1") (pinfunction "1_1") (pintype "passive"))
      (node (ref "C9") (pin "1") (pinfunction "1_1") (pintype "passive"))
      (node (ref "IC1") (pin "14") (pinfunction "VCC_14") (pintype "power_in"))
      (node (ref "IC1") (pin "24") (pinfunction "VCC_24") (pintype "power_in"))
      (node (ref "IC1") (pin "34") (pinfunction "VCC_34") (pintype "power_in"))
      (node (ref "IC1") (pin "4") (pinfunction "AVCC-B_4") (pintype "power_in"))
      (node (ref "IC1") (pin "44") (pinfunction "VCC_44") (pintype "power_in"))
      (node (ref "IC1") (pin "51") (pinfunction "PF6(RXD1/MISO)_51") (pintype "bidirectional"))
      (node (ref "IC1") (pin "54") (pinfunction "VCC_54") (pintype "power_in"))
      (node (ref "IC1") (pin "64") (pinfunction "VCC_64") (pintype "power_in"))
      (node (ref "IC1") (pin "74") (pinfunction "VCC_74") (pintype "power_in"))
      (node (ref "IC1") (pin "83") (pinfunction "VCC_83") (pintype "power_in"))
      (node (ref "IC1") (pin "94") (pinfunction "AVCC-A_94") (pintype "power_in"))
      (node (ref "IC10") (pin "5") (pinfunction "VCC_5") (pintype "power_in"))
      (node (ref "IC3") (pin "4") (pinfunction "VCCIO_4") (pintype "power_in"))
      (node (ref "IC4") (pin "5") (pinfunction "OUT_5") (pintype "bidirectional"))
      (node (ref "IC6") (pin "1") (pinfunction "AVDD_1") (pintype "bidirectional"))
      (node (ref "IC7") (pin "5") (pinfunction "VCC_5") (pintype "power_in"))
      (node (ref "IC8") (pin "5") (pinfunction "VCC_5") (pintype "power_in"))
      (node (ref "IC9") (pin "5") (pinfunction "VCC_5") (pintype "power_in"))
      (node (ref "LED0") (pin "A1") (pinfunction "A_A1") (pintype "passive"))
      (node (ref "LED0") (pin "A2") (pinfunction "A_A2") (pintype "passive"))
      (node (ref "LED1") (pin "A1") (pinfunction "A_A1") (pintype "passive"))
      (node (ref "LED1") (pin "A2") (pinfunction "A_A2") (pintype "passive"))
      (node (ref "LED2") (pin "A1") (pinfunction "A_A1") (pintype "passive"))
      (node (ref "LED2") (pin "A2") (pinfunction "A_A2") (pintype "passive"))
      (node (ref "LED3") (pin "A1") (pinfunction "A_A1") (pintype "passive"))
      (node (ref "LED3") (pin "A2") (pinfunction "A_A2") (pintype "passive"))
      (node (ref "LED4") (pin "A1") (pinfunction "A_A1") (pintype "passive"))
      (node (ref "LED4") (pin "A2") (pinfunction "A_A2") (pintype "passive"))
      (node (ref "LED5") (pin "A1") (pinfunction "A_A1") (pintype "passive"))
      (node (ref "LED5") (pin "A2") (pinfunction "A_A2") (pintype "passive"))
      (node (ref "OSC") (pin "P$4") (pinfunction "VDD_P$4") (pintype "passive"))
      (node (ref "PDI") (pin "2") (pinfunction "2_2") (pintype "passive"))
      (node (ref "R55") (pin "2") (pinfunction "2_2") (pintype "passive"))
      (node (ref "R68") (pin "2") (pinfunction "2_2") (pintype "passive"))
      (node (ref "U1") (pin "23") (pinfunction "VCC_B_23") (pintype "input"))
      (node (ref "U1") (pin "24") (pinfunction "VCC_B_24") (pintype "input"))
      (node (ref "U2") (pin "23") (pinfunction "VCC_B_23") (pintype "input"))
      (node (ref "U2") (pin "24") (pinfunction "VCC_B_24") (pintype "input"))
    )
    (net (code "2") (name "+5V") (class "Default")
      (node (ref "+5V_TP") (pin "TP") (pinfunction "TP_TP") (pintype "input"))
      (node (ref "C10") (pin "1") (pinfunction "1_1") (pintype "passive"))
      (node (ref "C23") (pin "1") (pinfunction "1_1") (pintype "passive"))
      (node (ref "C27") (pin "1") (pinfunction "1_1") (pintype "passive"))
      (node (ref "C28") (pin "1") (pinfunction "1_1") (pintype "passive"))
      (node (ref "C37") (pin "1") (pinfunction "1_1") (pintype "passive"))
      (node (ref "C38") (pin "1") (pinfunction "1_1") (pintype "passive"))
      (node (ref "C39") (pin "+") (pinfunction "+_+") (pintype "passive"))
      (node (ref "C40") (pin "1") (pinfunction "1_1") (pintype "passive"))
      (node (ref "C5") (pin "1") (pinfunction "1_1") (pintype "passive"))
      (node (ref "C52") (pin "1") (pinfunction "1_1") (pintype "passive"))
      (node (ref "IC3") (pin "20") (pinfunction "VCC_20") (pintype "power_in"))
      (node (ref "IC4") (pin "1") (pinfunction "IN_1") (pintype "bidirectional"))
      (node (ref "IC4") (pin "3") (pinfunction "EN_3") (pintype "bidirectional"))
      (node (ref "IC5") (pin "1") (pinfunction "IN_1") (pintype "bidirectional"))
      (node (ref "IC5") (pin "3") (pinfunction "EN_3") (pintype "bidirectional"))
      (node (ref "L1") (pin "1") (pinfunction "1_1") (pintype "passive"))
      (node (ref "SV1") (pin "10") (pinfunction "10_10") (pintype "passive"))
      (node (ref "U1") (pin "1") (pinfunction "VCC_A_1") (pintype "input"))
      (node (ref "U2") (pin "1") (pinfunction "VCC_A_1") (pintype "input"))
      (node (ref "U3") (pin "14") (pinfunction "VCC_14") (pintype "input"))
    )
    (net (code "3") (name "/5VUSB") (class "Default")
      (node (ref "C3") (pin "1") (pinfunction "1_1") (pintype "passive"))
      (node (ref "IC2") (pin "P$5") (pinfunction "VBUS_P$5") (pintype "bidirectional"))
      (node (ref "L1") (pin "2") (pinfunction "2_2") (pintype "passive"))
      (node (ref "USB") (pin "P$1") (pinfunction "1_P$1") (pintype "bidirectional"))
    )
    (net (code "4") (name "/AUX_IN0") (class "Default")
      (node (ref "IC10") (pin "2") (pinfunction "I_2") (pintype "input"))
      (node (ref "R16") (pin "1") (pinfunction "1_1") (pintype "passive"))
      (node (ref "SV1") (pin "6") (pinfunction "6_6") (pintype "passive"))
    )
    (net (code "5") (name "/AUX_IN0_UC") (class "Default")
      (node (ref "IC1") (pin "37") (pinfunction "PE2(OC0C/RXD0)_37") (pintype "bidirectional"))
      (node (ref "IC1") (pin "39") (pinfunction "PE4(OC1A/~{SS})_39") (pintype "bidirectional"))
      (node (ref "IC10") (pin "4") (pinfunction "O_4") (pintype "tri_state"))
    )
    (net (code "6") (name "/AUX_IN1") (class "Default")
      (node (ref "IC7") (pin "2") (pinfunction "I_2") (pintype "input"))
      (node (ref "R17") (pin "1") (pinfunction "1_1") (pintype "passive"))
      (node (ref "SV1") (pin "7") (pinfunction "7_7") (pintype "passive"))
    )
    (net (code "7") (name "/AUX_IN1_UC") (class "Default")
      (node (ref "IC1") (pin "40") (pinfunction "PE5(OC1B/XCK1/MOSI)_40") (pintype "bidirectional"))
      (node (ref "IC7") (pin "4") (pinfunction "O_4") (pintype "tri_state"))
    )
    (net (code "8") (name "/BNC_IOS_DIR") (class "Default")
      (node (ref "U2") (pin "2") (pinfunction "DIR_2") (pintype "input"))
      (node (ref "U3") (pin "3") (pinfunction "1Y_3") (pintype "bidirectional"))
    )
    (net (code "9") (name "/BNC_IOS_ENBL") (class "Default")
      (node (ref "R15") (pin "2") (pinfunction "2_2") (pintype "passive"))
      (node (ref "U2") (pin "22") (pinfunction "OE_22") (pintype "input"))
      (node (ref "U3") (pin "6") (pinfunction "2B_6") (pintype "bidirectional"))
    )
    (net (code "10") (name "/CLOCK_IN") (class "Default")
      (node (ref "CLKIN") (pin "4") (pinfunction "4_4") (pintype "passive"))
      (node (ref "IC1") (pin "21") (pinfunction "PC6(MISO/RXD1)_21") (pintype "bidirectional"))
      (node (ref "IC8") (pin "2") (pinfunction "I_2") (pintype "input"))
      (node (ref "R3") (pin "2") (pinfunction "2_2") (pintype "passive"))
    )
    (net (code "11") (name "/CLOCK_OUT") (class "Default")
      (node (ref "IC1") (pin "22") (pinfunction "PC7(SCK/TXD1/CLKO/EVO)_22") (pintype "bidirectional"))
      (node (ref "IC9") (pin "2") (pinfunction "I_2") (pintype "input"))
    )
    (net (code "12") (name "/EN_CLOCK_IN") (class "Default")
      (node (ref "IC1") (pin "77") (pinfunction "PK2(A2/A10/A18)_77") (pintype "bidirectional"))
      (node (ref "IC8") (pin "1") (pinfunction "OE_1") (pintype "input"))
      (node (ref "R54") (pin "1") (pinfunction "1_1") (pintype "passive"))
    )
    (net (code "13") (name "/EN_CLOCK_OUT") (class "Default")
      (node (ref "IC1") (pin "76") (pinfunction "PK1(A1/A9/A17)_76") (pintype "bidirectional"))
      (node (ref "IC9") (pin "1") (pinfunction "OE_1") (pintype "input"))
      (node (ref "R55") (pin "1") (pinfunction "1_1") (pintype "passive"))
    )
    (net (code "14") (name "/FTDI_CTS") (class "Default")
      (node (ref "IC1") (pin "75") (pinfunction "PK0(A0/A8/A16)_75") (pintype "bidirectional"))
      (node (ref "IC3") (pin "11") (pinfunction "~{CTS}_11") (pintype "input"))
    )
    (net (code "15") (name "/FTDI_RTS") (class "Default")
      (node (ref "IC1") (pin "71") (pinfunction "PJ6(A10/D6/A6/A14)_71") (pintype "bidirectional"))
      (node (ref "IC3") (pin "3") (pinfunction "~{RTS}_3") (pintype "output"))
    )
    (net (code "16") (name "/FTDI_RXD") (class "Default")
      (node (ref "IC1") (pin "48") (pinfunction "PF3(OC0D/TXD0)_48") (pintype "bidirectional"))
      (node (ref "IC3") (pin "5") (pinfunction "RXD_5") (pintype "input"))
    )
    (net (code "17") (name "/FTDI_TXD") (class "Default")
      (node (ref "IC1") (pin "47") (pinfunction "PF2(OC0C/RXD0)_47") (pintype "bidirectional"))
      (node (ref "IC3") (pin "1") (pinfunction "TXD_1") (pintype "output"))
    )
    (net (code "18") (name "/IDE_IOS_DIR") (class "Default")
      (node (ref "U1") (pin "2") (pinfunction "DIR_2") (pintype "input"))
      (node (ref "U3") (pin "8") (pinfunction "3Y_8") (pintype "bidirectional"))
    )
    (net (code "19") (name "/IDE_IOS_ENBL") (class "Default")
      (node (ref "R14") (pin "2") (pinfunction "2_2") (pintype "passive"))
      (node (ref "U1") (pin "22") (pinfunction "OE_22") (pintype "input"))
      (node (ref "U3") (pin "11") (pinfunction "4Y_11") (pintype "bidirectional"))
    )
    (net (code "20") (name "/IO0") (class "Default")
      (node (ref "BNC0") (pin "1") (pinfunction "1_1") (pintype "passive"))
      (node (ref "R19") (pin "2") (pinfunction "2_2") (pintype "passive"))
      (node (ref "R4") (pin "1") (pinfunction "1_1") (pintype "passive"))
    )
    (net (code "21") (name "/IO0_UC") (class "Default")
      (node (ref "IC1") (pin "29") (pinfunction "PD4(OC1A/~{SS})_29") (pintype "bidirectional"))
      (node (ref "U2") (pin "21") (pinfunction "B0_21") (pintype "bidirectional"))
    )
    (net (code "22") (name "/IO1") (class "Default")
      (node (ref "BNC1") (pin "1") (pinfunction "1_1") (pintype "passive"))
      (node (ref "R38") (pin "2") (pinfunction "2_2") (pintype "passive"))
      (node (ref "R5") (pin "1") (pinfunction "1_1") (pintype "passive"))
    )
    (net (code "23") (name "/IO1_UC") (class "Default")
      (node (ref "IC1") (pin "28") (pinfunction "PD3(OC0D/TXD0)_28") (pintype "bidirectional"))
      (node (ref "U2") (pin "20") (pinfunction "B1_20") (pintype "bidirectional"))
    )
    (net (code "24") (name "/IO2") (class "Default")
      (node (ref "BNC2") (pin "1") (pinfunction "1_1") (pintype "passive"))
      (node (ref "R43") (pin "2") (pinfunction "2_2") (pintype "passive"))
      (node (ref "R6") (pin "1") (pinfunction "1_1") (pintype "passive"))
    )
    (net (code "25") (name "/IO2_UC") (class "Default")
      (node (ref "IC1") (pin "27") (pinfunction "PD2(OC0C/RXD0)_27") (pintype "bidirectional"))
      (node (ref "U2") (pin "19") (pinfunction "B2_19") (pintype "bidirectional"))
    )
    (net (code "26") (name "/IO3") (class "Default")
      (node (ref "BNC3") (pin "1") (pinfunction "1_1") (pintype "passive"))
      (node (ref "R46") (pin "2") (pinfunction "2_2") (pintype "passive"))
      (node (ref "R7") (pin "1") (pinfunction "1_1") (pintype "passive"))
    )
    (net (code "27") (name "/IO3_UC") (class "Default")
      (node (ref "IC1") (pin "26") (pinfunction "PD1(OC0B/XCK0/SCL)_26") (pintype "bidirectional"))
      (node (ref "U2") (pin "18") (pinfunction "B3_18") (pintype "bidirectional"))
    )
    (net (code "28") (name "/IO4") (class "Default")
      (node (ref "BNC4") (pin "1") (pinfunction "1_1") (pintype "passive"))
      (node (ref "R47") (pin "2") (pinfunction "2_2") (pintype "passive"))
      (node (ref "R8") (pin "1") (pinfunction "1_1") (pintype "passive"))
    )
    (net (code "29") (name "/IO4_UC") (class "Default")
      (node (ref "IC1") (pin "25") (pinfunction "PD0(OC0A/SDA)_25") (pintype "bidirectional"))
      (node (ref "U2") (pin "17") (pinfunction "B4_17") (pintype "bidirectional"))
    )
    (net (code "30") (name "/IO5") (class "Default")
      (node (ref "R48") (pin "1") (pinfunction "1_1") (pintype "passive"))
      (node (ref "R9") (pin "1") (pinfunction "1_1") (pintype "passive"))
      (node (ref "SV1") (pin "1") (pinfunction "1_1") (pintype "passive"))
    )
    (net (code "31") (name "/IO5_UC") (class "Default")
      (node (ref "IC1") (pin "15") (pinfunction "PC0(OC0A/SDA)_15") (pintype "bidirectional"))
      (node (ref "U1") (pin "21") (pinfunction "B0_21") (pintype "bidirectional"))
    )
    (net (code "32") (name "/IO6") (class "Default")
      (node (ref "R10") (pin "1") (pinfunction "1_1") (pintype "passive"))
      (node (ref "R49") (pin "1") (pinfunction "1_1") (pintype "passive"))
      (node (ref "SV1") (pin "2") (pinfunction "2_2") (pintype "passive"))
    )
    (net (code "33") (name "/IO6_UC") (class "Default")
      (node (ref "IC1") (pin "16") (pinfunction "PC1(OC0B/XCK0/SCL)_16") (pintype "bidirectional"))
      (node (ref "U1") (pin "20") (pinfunction "B1_20") (pintype "bidirectional"))
    )
    (net (code "34") (name "/IO7") (class "Default")
      (node (ref "R11") (pin "1") (pinfunction "1_1") (pintype "passive"))
      (node (ref "R50") (pin "1") (pinfunction "1_1") (pintype "passive"))
      (node (ref "SV1") (pin "3") (pinfunction "3_3") (pintype "passive"))
    )
    (net (code "35") (name "/IO7_UC") (class "Default")
      (node (ref "IC1") (pin "17") (pinfunction "PC2(OC0C/RXD0)_17") (pintype "bidirectional"))
      (node (ref "U1") (pin "19") (pinfunction "B2_19") (pintype "bidirectional"))
    )
    (net (code "36") (name "/IO8") (class "Default")
      (node (ref "R12") (pin "1") (pinfunction "1_1") (pintype "passive"))
      (node (ref "R51") (pin "1") (pinfunction "1_1") (pintype "passive"))
      (node (ref "SV1") (pin "4") (pinfunction "4_4") (pintype "passive"))
    )
    (net (code "37") (name "/IO8_UC") (class "Default")
      (node (ref "IC1") (pin "18") (pinfunction "PC3(OC0D/TXD0)_18") (pintype "bidirectional"))
      (node (ref "U1") (pin "18") (pinfunction "B3_18") (pintype "bidirectional"))
    )
    (net (code "38") (name "/IO9") (class "Default")
      (node (ref "R13") (pin "1") (pinfunction "1_1") (pintype "passive"))
      (node (ref "R52") (pin "1") (pinfunction "1_1") (pintype "passive"))
      (node (ref "SV1") (pin "5") (pinfunction "5_5") (pintype "passive"))
    )
    (net (code "39") (name "/IO9_UC") (class "Default")
      (node (ref "IC1") (pin "35") (pinfunction "PE0(OC0A/SDA)_35") (pintype "bidirectional"))
      (node (ref "U1") (pin "17") (pinfunction "B4_17") (pintype "bidirectional"))
    )
    (net (code "40") (name "/LED_I0") (class "Default")
      (node (ref "IC1") (pin "55") (pinfunction "PH0(~{WE})_55") (pintype "bidirectional"))
      (node (ref "R20") (pin "1") (pinfunction "1_1") (pintype "passive"))
    )
    (net (code "41") (name "/LED_I1") (class "Default")
      (node (ref "IC1") (pin "56") (pinfunction "PH1(~{CAS}/~{RE})_56") (pintype "bidirectional"))
      (node (ref "R21") (pin "1") (pinfunction "1_1") (pintype "passive"))
    )
    (net (code "42") (name "/LED_I2") (class "Default")
      (node (ref "IC1") (pin "57") (pinfunction "PH2(~{RAS}/ALE1)_57") (pintype "bidirectional"))
      (node (ref "R22") (pin "1") (pinfunction "1_1") (pintype "passive"))
    )
    (net (code "43") (name "/LED_I3") (class "Default")
      (node (ref "IC1") (pin "58") (pinfunction "PH3(~{DOM}/ALE2)_58") (pintype "bidirectional"))
      (node (ref "R23") (pin "1") (pinfunction "1_1") (pintype "passive"))
    )
    (net (code "44") (name "/LED_I4") (class "Default")
      (node (ref "IC1") (pin "59") (pinfunction "PH4(BA0/~{CS0}/A16)_59") (pintype "bidirectional"))
      (node (ref "R24") (pin "1") (pinfunction "1_1") (pintype "passive"))
    )
    (net (code "45") (name "/LED_I5") (class "Default")
      (node (ref "IC1") (pin "60") (pinfunction "PH5(BA1/~{CS1}/A17)_60") (pintype "bidirectional"))
      (node (ref "R26") (pin "1") (pinfunction "1_1") (pintype "passive"))
    )
    (net (code "46") (name "/LED_I6") (class "Default")
      (node (ref "IC1") (pin "61") (pinfunction "PH6(CKE/~{CS2}/A18)_61") (pintype "bidirectional"))
      (node (ref "R27") (pin "1") (pinfunction "1_1") (pintype "passive"))
    )
    (net (code "47") (name "/LED_I7") (class "Default")
      (node (ref "IC1") (pin "62") (pinfunction "PH7(CLK/~{CS3}/A19)_62") (pintype "bidirectional"))
      (node (ref "R28") (pin "1") (pinfunction "1_1") (pintype "passive"))
    )
    (net (code "48") (name "/LED_I8") (class "Default")
      (node (ref "IC1") (pin "65") (pinfunction "PJ0(D0/A0/A8)_65") (pintype "bidirectional"))
      (node (ref "R29") (pin "1") (pinfunction "1_1") (pintype "passive"))
    )
    (net (code "49") (name "/LED_I9") (class "Default")
      (node (ref "IC1") (pin "66") (pinfunction "PJ1(D1/A1/A9)_66") (pintype "bidirectional"))
      (node (ref "R30") (pin "1") (pinfunction "1_1") (pintype "passive"))
    )
    (net (code "50") (name "/LED_PWR") (class "Default")
      (node (ref "IC1") (pin "67") (pinfunction "PJ2(D2/A2/A10)_67") (pintype "bidirectional"))
      (node (ref "R25") (pin "1") (pinfunction "1_1") (pintype "passive"))
    )
    (net (code "51") (name "/PDI_CLK") (class "Default")
      (node (ref "C51") (pin "1") (pinfunction "1_1") (pintype "passive"))
      (node (ref "IC1") (pin "90") (pinfunction "PDI-CLK/~{RESET}_90") (pintype "input"))
      (node (ref "PDI") (pin "5") (pinfunction "5_5") (pintype "passive"))
      (node (ref "R68") (pin "1") (pinfunction "1_1") (pintype "passive"))
    )
    (net (code "52") (name "/PDI_DATA") (class "Default")
      (node (ref "IC1") (pin "89") (pinfunction "PDI-DATA_89") (pintype "bidirectional"))
      (node (ref "PDI") (pin "1") (pinfunction "1_1") (pintype "passive"))
    )
    (net (code "53") (name "/STATE") (class "Default")
      (node (ref "IC1") (pin "1") (pinfunction "PA6(ADCA6)_1") (pintype "bidirectional"))
      (node (ref "R31") (pin "1") (pinfunction "1_1") (pintype "passive"))
    )
    (net (code "54") (name "/U_BNC_IOS_DIR") (class "Default")
      (node (ref "IC1") (pin "32") (pinfunction "PD7(TXD1/SCK/CLKO/EVO)_32") (pintype "bidirectional"))
      (node (ref "U3") (pin "2") (pinfunction "1A_2") (pintype "bidirectional"))
    )
    (net (code "55") (name "/U_BNC_IOS_ENBL") (class "Default")
      (node (ref "IC1") (pin "31") (pinfunction "PD6(RXD1/MISO)_31") (pintype "bidirectional"))
      (node (ref "U3") (pin "5") (pinfunction "2A_5") (pintype "bidirectional"))
    )
    (net (code "56") (name "/U_IDE_IOS_DIR") (class "Default")
      (node (ref "IC1") (pin "10") (pinfunction "PB5(ADCB5/TDI)_10") (pintype "bidirectional"))
      (node (ref "U3") (pin "9") (pinfunction "3A_9") (pintype "bidirectional"))
    )
    (net (code "57") (name "/U_IDE_IOS_ENBL") (class "Default")
      (node (ref "IC1") (pin "11") (pinfunction "PB6(ADCB6/TCK)_11") (pintype "bidirectional"))
      (node (ref "U3") (pin "12") (pinfunction "4A_12") (pintype "bidirectional"))
    )
    (net (code "58") (name "GND") (class "Default")
      (node (ref "BNC0") (pin "2") (pinfunction "2_2") (pintype "passive"))
      (node (ref "BNC0") (pin "3") (pinfunction "2_3") (pintype "passive"))
      (node (ref "BNC1") (pin "2") (pinfunction "2_2") (pintype "passive"))
      (node (ref "BNC1") (pin "3") (pinfunction "2_3") (pintype "passive"))
      (node (ref "BNC2") (pin "2") (pinfunction "2_2") (pintype "passive"))
      (node (ref "BNC2") (pin "3") (pinfunction "2_3") (pintype "passive"))
      (node (ref "BNC3") (pin "2") (pinfunction "2_2") (pintype "passive"))
      (node (ref "BNC3") (pin "3") (pinfunction "2_3") (pintype "passive"))
      (node (ref "BNC4") (pin "2") (pinfunction "2_2") (pintype "passive"))
      (node (ref "BNC4") (pin "3") (pinfunction "2_3") (pintype "passive"))
      (node (ref "C1") (pin "2") (pinfunction "2_2") (pintype "passive"))
      (node (ref "C10") (pin "2") (pinfunction "2_2") (pintype "passive"))
      (node (ref "C11") (pin "2") (pinfunction "2_2") (pintype "passive"))
      (node (ref "C12") (pin "2") (pinfunction "2_2") (pintype "passive"))
      (node (ref "C13") (pin "2") (pinfunction "2_2") (pintype "passive"))
      (node (ref "C14") (pin "2") (pinfunction "2_2") (pintype "passive"))
      (node (ref "C15") (pin "2") (pinfunction "2_2") (pintype "passive"))
      (node (ref "C16") (pin "2") (pinfunction "2_2") (pintype "passive"))
      (node (ref "C17") (pin "2") (pinfunction "2_2") (pintype "passive"))
      (node (ref "C18") (pin "2") (pinfunction "2_2") (pintype "passive"))
      (node (ref "C19") (pin "2") (pinfunction "2_2") (pintype "passive"))
      (node (ref "C2") (pin "2") (pinfunction "2_2") (pintype "passive"))
      (node (ref "C20") (pin "2") (pinfunction "2_2") (pintype "passive"))
      (node (ref "C21") (pin "2") (pinfunction "2_2") (pintype "passive"))
      (node (ref "C22") (pin "2") (pinfunction "2_2") (pintype "passive"))
      (node (ref "C23") (pin "2") (pinfunction "2_2") (pintype "passive"))
      (node (ref "C24") (pin "2") (pinfunction "2_2") (pintype "passive"))
      (node (ref "C25") (pin "2") (pinfunction "2_2") (pintype "passive"))
      (node (ref "C27") (pin "2") (pinfunction "2_2") (pintype "passive"))
      (node (ref "C28") (pin "2") (pinfunction "2_2") (pintype "passive"))
      (node (ref "C29") (pin "2") (pinfunction "2_2") (pintype "passive"))
      (node (ref "C3") (pin "2") (pinfunction "2_2") (pintype "passive"))
      (node (ref "C30") (pin "2") (pinfunction "2_2") (pintype "passive"))
      (node (ref "C31") (pin "2") (pinfunction "2_2") (pintype "passive"))
      (node (ref "C32") (pin "2") (pinfunction "2_2") (pintype "passive"))
      (node (ref "C33") (pin "2") (pinfunction "2_2") (pintype "passive"))
      (node (ref "C34") (pin "2") (pinfunction "2_2") (pintype "passive"))
      (node (ref "C35") (pin "2") (pinfunction "2_2") (pintype "passive"))
      (node (ref "C36") (pin "2") (pinfunction "2_2") (pintype "passive"))
      (node (ref "C37") (pin "2") (pinfunction "2_2") (pintype "passive"))
      (node (ref "C38") (pin "2") (pinfunction "2_2") (pintype "passive"))
      (node (ref "C39") (pin "-") (pinfunction "-_-") (pintype "passive"))
      (node (ref "C4") (pin "2") (pinfunction "2_2") (pintype "passive"))
      (node (ref "C40") (pin "2") (pinfunction "2_2") (pintype "passive"))
      (node (ref "C41") (pin "2") (pinfunction "2_2") (pintype "passive"))
      (node (ref "C42") (pin "2") (pinfunction "2_2") (pintype "passive"))
      (node (ref "C43") (pin "2") (pinfunction "2_2") (pintype "passive"))
      (node (ref "C44") (pin "2") (pinfunction "2_2") (pintype "passive"))
      (node (ref "C45") (pin "2") (pinfunction "2_2") (pintype "passive"))
      (node (ref "C46") (pin "2") (pinfunction "2_2") (pintype "passive"))
      (node (ref "C47") (pin "2") (pinfunction "2_2") (pintype "passive"))
      (node (ref "C48") (pin "2") (pinfunction "2_2") (pintype "passive"))
      (node (ref "C49") (pin "2") (pinfunction "2_2") (pintype "passive"))
      (node (ref "C5") (pin "2") (pinfunction "2_2") (pintype "passive"))
      (node (ref "C50") (pin "2") (pinfunction "2_2") (pintype "passive"))
      (node (ref "C51") (pin "2") (pinfunction "2_2") (pintype "passive"))
      (node (ref "C52") (pin "2") (pinfunction "2_2") (pintype "passive"))
      (node (ref "C6") (pin "2") (pinfunction "2_2") (pintype "passive"))
      (node (ref "C7") (pin "2") (pinfunction "2_2") (pintype "passive"))
      (node (ref "C9") (pin "2") (pinfunction "2_2") (pintype "passive"))
      (node (ref "CLKIN") (pin "5") (pinfunction "5_5") (pintype "passive"))
      (node (ref "GND_TP0") (pin "TP") (pinfunction "TP_TP") (pintype "input"))
      (node (ref "GND_TP1") (pin "TP") (pinfunction "TP_TP") (pintype "input"))
      (node (ref "IC1") (pin "13") (pinfunction "GND_13") (pintype "power_in"))
      (node (ref "IC1") (pin "23") (pinfunction "GND_23") (pintype "power_in"))
      (node (ref "IC1") (pin "3") (pinfunction "GND_3") (pintype "power_in"))
      (node (ref "IC1") (pin "33") (pinfunction "GND_33") (pintype "power_in"))
      (node (ref "IC1") (pin "43") (pinfunction "GND_43") (pintype "power_in"))
      (node (ref "IC1") (pin "53") (pinfunction "GND_53") (pintype "power_in"))
      (node (ref "IC1") (pin "63") (pinfunction "GND_63") (pintype "power_in"))
      (node (ref "IC1") (pin "73") (pinfunction "GND_73") (pintype "power_in"))
      (node (ref "IC1") (pin "84") (pinfunction "GND_84") (pintype "power_in"))
      (node (ref "IC1") (pin "93") (pinfunction "GND_93") (pintype "power_in"))
      (node (ref "IC10") (pin "1") (pinfunction "OE_1") (pintype "input"))
      (node (ref "IC10") (pin "3") (pinfunction "GND_3") (pintype "power_in"))
      (node (ref "IC2") (pin "P$2") (pinfunction "GND_P$2") (pintype "bidirectional"))
      (node (ref "IC3") (pin "18") (pinfunction "GND_18") (pintype "power_in"))
      (node (ref "IC3") (pin "21") (pinfunction "GND_21") (pintype "power_in"))
      (node (ref "IC3") (pin "25") (pinfunction "GND_25") (pintype "power_in"))
      (node (ref "IC3") (pin "26") (pinfunction "TEST_26") (pintype "input"))
      (node (ref "IC3") (pin "7") (pinfunction "GND_7") (pintype "power_in"))
      (node (ref "IC4") (pin "2") (pinfunction "GND_2") (pintype "bidirectional"))
      (node (ref "IC5") (pin "2") (pinfunction "GND_2") (pintype "bidirectional"))
      (node (ref "IC6") (pin "4") (pinfunction "AGND_4") (pintype "bidirectional"))
      (node (ref "IC7") (pin "1") (pinfunction "OE_1") (pintype "input"))
      (node (ref "IC7") (pin "3") (pinfunction "GND_3") (pintype "power_in"))
      (node (ref "IC8") (pin "3") (pinfunction "GND_3") (pintype "power_in"))
      (node (ref "IC9") (pin "3") (pinfunction "GND_3") (pintype "power_in"))
      (node (ref "OSC") (pin "P$2") (pinfunction "GND_P$2") (pintype "passive"))
      (node (ref "PDI") (pin "6") (pinfunction "6_6") (pintype "passive"))
      (node (ref "R10") (pin "2") (pinfunction "2_2") (pintype "passive"))
      (node (ref "R11") (pin "2") (pinfunction "2_2") (pintype "passive"))
      (node (ref "R12") (pin "2") (pinfunction "2_2") (pintype "passive"))
      (node (ref "R13") (pin "2") (pinfunction "2_2") (pintype "passive"))
      (node (ref "R14") (pin "1") (pinfunction "1_1") (pintype "passive"))
      (node (ref "R15") (pin "1") (pinfunction "1_1") (pintype "passive"))
      (node (ref "R16") (pin "2") (pinfunction "2_2") (pintype "passive"))
      (node (ref "R17") (pin "2") (pinfunction "2_2") (pintype "passive"))
      (node (ref "R19") (pin "1") (pinfunction "1_1") (pintype "passive"))
      (node (ref "R38") (pin "1") (pinfunction "1_1") (pintype "passive"))
      (node (ref "R43") (pin "1") (pinfunction "1_1") (pintype "passive"))
      (node (ref "R46") (pin "1") (pinfunction "1_1") (pintype "passive"))
      (node (ref "R47") (pin "1") (pinfunction "1_1") (pintype "passive"))
      (node (ref "R53") (pin "2") (pinfunction "2_2") (pintype "passive"))
      (node (ref "R54") (pin "2") (pinfunction "2_2") (pintype "passive"))
      (node (ref "R56") (pin "2") (pinfunction "2_2") (pintype "passive"))
      (node (ref "R57") (pin "2") (pinfunction "2_2") (pintype "passive"))
      (node (ref "R58") (pin "2") (pinfunction "2_2") (pintype "passive"))
      (node (ref "R59") (pin "2") (pinfunction "2_2") (pintype "passive"))
      (node (ref "R60") (pin "2") (pinfunction "2_2") (pintype "passive"))
      (node (ref "R61") (pin "2") (pinfunction "2_2") (pintype "passive"))
      (node (ref "R62") (pin "2") (pinfunction "2_2") (pintype "passive"))
      (node (ref "R63") (pin "2") (pinfunction "2_2") (pintype "passive"))
      (node (ref "R64") (pin "2") (pinfunction "2_2") (pintype "passive"))
      (node (ref "R65") (pin "2") (pinfunction "2_2") (pintype "passive"))
      (node (ref "R66") (pin "2") (pinfunction "2_2") (pintype "passive"))
      (node (ref "R67") (pin "2") (pinfunction "2_2") (pintype "passive"))
      (node (ref "R69") (pin "2") (pinfunction "2_2") (pintype "passive"))
      (node (ref "R9") (pin "2") (pinfunction "2_2") (pintype "passive"))
      (node (ref "SV1") (pin "9") (pinfunction "9_9") (pintype "passive"))
      (node (ref "T10") (pin "2") (pinfunction "E_2") (pintype "passive"))
      (node (ref "T11") (pin "2") (pinfunction "E_2") (pintype "passive"))
      (node (ref "T12") (pin "2") (pinfunction "E_2") (pintype "passive"))
      (node (ref "T13") (pin "2") (pinfunction "E_2") (pintype "passive"))
      (node (ref "T2") (pin "2") (pinfunction "E_2") (pintype "passive"))
      (node (ref "T3") (pin "2") (pinfunction "E_2") (pintype "passive"))
      (node (ref "T4") (pin "2") (pinfunction "E_2") (pintype "passive"))
      (node (ref "T5") (pin "2") (pinfunction "E_2") (pintype "passive"))
      (node (ref "T6") (pin "2") (pinfunction "E_2") (pintype "passive"))
      (node (ref "T7") (pin "2") (pinfunction "E_2") (pintype "passive"))
      (node (ref "T8") (pin "2") (pinfunction "E_2") (pintype "passive"))
      (node (ref "T9") (pin "2") (pinfunction "E_2") (pintype "passive"))
      (node (ref "U1") (pin "11") (pinfunction "GND_11") (pintype "bidirectional"))
      (node (ref "U1") (pin "12") (pinfunction "GND_12") (pintype "bidirectional"))
      (node (ref "U1") (pin "13") (pinfunction "GND_13") (pintype "bidirectional"))
      (node (ref "U2") (pin "11") (pinfunction "GND_11") (pintype "bidirectional"))
      (node (ref "U2") (pin "12") (pinfunction "GND_12") (pintype "bidirectional"))
      (node (ref "U2") (pin "13") (pinfunction "GND_13") (pintype "bidirectional"))
      (node (ref "U3") (pin "1") (pinfunction "~{1OE}_1") (pintype "bidirectional"))
      (node (ref "U3") (pin "10") (pinfunction "~{3OE}_10") (pintype "bidirectional"))
      (node (ref "U3") (pin "13") (pinfunction "~{4OE}_13") (pintype "bidirectional"))
      (node (ref "U3") (pin "4") (pinfunction "~{2OE}_4") (pintype "bidirectional"))
      (node (ref "U3") (pin "7") (pinfunction "GND_7") (pintype "bidirectional"))
      (node (ref "USB") (pin "P$5") (pinfunction "5_P$5") (pintype "bidirectional"))
    )
    (net (code "59") (name "Net-(CLKIN-Pad1)") (class "Default")
      (node (ref "CLKIN") (pin "1") (pinfunction "1_1") (pintype "passive"))
      (node (ref "R2") (pin "2") (pinfunction "2_2") (pintype "passive"))
      (node (ref "R3") (pin "1") (pinfunction "1_1") (pintype "passive"))
    )
    (net (code "60") (name "Net-(IC1-PE3(OC0D{slash}TXD0))") (class "Default")
      (node (ref "IC1") (pin "38") (pinfunction "PE3(OC0D/TXD0)_38") (pintype "bidirectional"))
      (node (ref "R53") (pin "1") (pinfunction "1_1") (pintype "passive"))
    )
    (net (code "61") (name "Net-(IC1-PR1(XTAL1))") (class "Default")
      (node (ref "IC1") (pin "92") (pinfunction "PR1(XTAL1)_92") (pintype "bidirectional"))
      (node (ref "OSC") (pin "P$3") (pinfunction "OUTPUT_P$3") (pintype "passive"))
    )
    (net (code "62") (name "Net-(IC3-3V3OUT)") (class "Default")
      (node (ref "C7") (pin "1") (pinfunction "1_1") (pintype "passive"))
      (node (ref "IC3") (pin "17") (pinfunction "3V3OUT_17") (pintype "output"))
    )
    (net (code "63") (name "Net-(IC3-USBDM)") (class "Default")
      (node (ref "C6") (pin "1") (pinfunction "1_1") (pintype "passive"))
      (node (ref "IC2") (pin "P$6") (pinfunction "IO1_P$6") (pintype "bidirectional"))
      (node (ref "IC3") (pin "16") (pinfunction "USBDM_16") (pintype "bidirectional"))
    )
    (net (code "64") (name "Net-(IC3-USBDP)") (class "Default")
      (node (ref "C4") (pin "1") (pinfunction "1_1") (pintype "passive"))
      (node (ref "IC2") (pin "P$4") (pinfunction "IO2_P$4") (pintype "bidirectional"))
      (node (ref "IC3") (pin "15") (pinfunction "USBDP_15") (pintype "bidirectional"))
    )
    (net (code "65") (name "Net-(IC5-OUT)") (class "Default")
      (node (ref "C24") (pin "1") (pinfunction "1_1") (pintype "passive"))
      (node (ref "IC5") (pin "5") (pinfunction "OUT_5") (pintype "bidirectional"))
      (node (ref "R2") (pin "1") (pinfunction "1_1") (pintype "passive"))
    )
    (net (code "66") (name "Net-(IC6-A1)") (class "Default")
      (node (ref "IC6") (pin "2") (pinfunction "A1_2") (pintype "bidirectional"))
      (node (ref "IC8") (pin "4") (pinfunction "O_4") (pintype "tri_state"))
      (node (ref "IC9") (pin "4") (pinfunction "O_4") (pintype "tri_state"))
    )
    (net (code "67") (name "Net-(IC6-B1)") (class "Default")
      (node (ref "CLKOUT") (pin "4") (pinfunction "4_4") (pintype "passive"))
      (node (ref "IC6") (pin "6") (pinfunction "B1_6") (pintype "bidirectional"))
    )
    (net (code "68") (name "Net-(IC6-BGND)") (class "Default")
      (node (ref "C26") (pin "2") (pinfunction "2_2") (pintype "passive"))
      (node (ref "CLKOUT") (pin "5") (pinfunction "5_5") (pintype "passive"))
      (node (ref "IC6") (pin "5") (pinfunction "BGND_5") (pintype "bidirectional"))
    )
    (net (code "69") (name "Net-(IC6-BVDD)") (class "Default")
      (node (ref "C26") (pin "1") (pinfunction "1_1") (pintype "passive"))
      (node (ref "CLKOUT") (pin "1") (pinfunction "1_1") (pintype "passive"))
      (node (ref "IC6") (pin "8") (pinfunction "BVDD_8") (pintype "bidirectional"))
    )
    (net (code "70") (name "Net-(LED0A-C)") (class "Default")
      (node (ref "LED0") (pin "C1") (pinfunction "C_C1") (pintype "passive"))
      (node (ref "R39") (pin "1") (pinfunction "1_1") (pintype "passive"))
    )
    (net (code "71") (name "Net-(LED0B-C)") (class "Default")
      (node (ref "LED0") (pin "C2") (pinfunction "C_C2") (pintype "passive"))
      (node (ref "R32") (pin "1") (pinfunction "1_1") (pintype "passive"))
    )
    (net (code "72") (name "Net-(LED1A-C)") (class "Default")
      (node (ref "LED1") (pin "C1") (pinfunction "C_C1") (pintype "passive"))
      (node (ref "R40") (pin "1") (pinfunction "1_1") (pintype "passive"))
    )
    (net (code "73") (name "Net-(LED1B-C)") (class "Default")
      (node (ref "LED1") (pin "C2") (pinfunction "C_C2") (pintype "passive"))
      (node (ref "R33") (pin "1") (pinfunction "1_1") (pintype "passive"))
    )
    (net (code "74") (name "Net-(LED2A-C)") (class "Default")
      (node (ref "LED2") (pin "C1") (pinfunction "C_C1") (pintype "passive"))
      (node (ref "R41") (pin "1") (pinfunction "1_1") (pintype "passive"))
    )
    (net (code "75") (name "Net-(LED2B-C)") (class "Default")
      (node (ref "LED2") (pin "C2") (pinfunction "C_C2") (pintype "passive"))
      (node (ref "R34") (pin "1") (pinfunction "1_1") (pintype "passive"))
    )
    (net (code "76") (name "Net-(LED3A-C)") (class "Default")
      (node (ref "LED3") (pin "C1") (pinfunction "C_C1") (pintype "passive"))
      (node (ref "R42") (pin "1") (pinfunction "1_1") (pintype "passive"))
    )
    (net (code "77") (name "Net-(LED3B-C)") (class "Default")
      (node (ref "LED3") (pin "C2") (pinfunction "C_C2") (pintype "passive"))
      (node (ref "R35") (pin "1") (pinfunction "1_1") (pintype "passive"))
    )
    (net (code "78") (name "Net-(LED4A-C)") (class "Default")
      (node (ref "LED4") (pin "C1") (pinfunction "C_C1") (pintype "passive"))
      (node (ref "R44") (pin "1") (pinfunction "1_1") (pintype "passive"))
    )
    (net (code "79") (name "Net-(LED4B-C)") (class "Default")
      (node (ref "LED4") (pin "C2") (pinfunction "C_C2") (pintype "passive"))
      (node (ref "R36") (pin "1") (pinfunction "1_1") (pintype "passive"))
    )
    (net (code "80") (name "Net-(LED5A-C)") (class "Default")
      (node (ref "LED5") (pin "C1") (pinfunction "C_C1") (pintype "passive"))
      (node (ref "R45") (pin "1") (pinfunction "1_1") (pintype "passive"))
    )
    (net (code "81") (name "Net-(LED5B-C)") (class "Default")
      (node (ref "LED5") (pin "C2") (pinfunction "C_C2") (pintype "passive"))
      (node (ref "R37") (pin "1") (pinfunction "1_1") (pintype "passive"))
    )
    (net (code "82") (name "Net-(T2-B)") (class "Default")
      (node (ref "R20") (pin "2") (pinfunction "2_2") (pintype "passive"))
      (node (ref "T2") (pin "1") (pinfunction "B_1") (pintype "passive"))
    )
    (net (code "83") (name "Net-(T2-C)") (class "Default")
      (node (ref "R32") (pin "2") (pinfunction "2_2") (pintype "passive"))
      (node (ref "T2") (pin "3") (pinfunction "C_3") (pintype "passive"))
    )
    (net (code "84") (name "Net-(T3-B)") (class "Default")
      (node (ref "R26") (pin "2") (pinfunction "2_2") (pintype "passive"))
      (node (ref "T3") (pin "1") (pinfunction "B_1") (pintype "passive"))
    )
    (net (code "85") (name "Net-(T3-C)") (class "Default")
      (node (ref "R39") (pin "2") (pinfunction "2_2") (pintype "passive"))
      (node (ref "T3") (pin "3") (pinfunction "C_3") (pintype "passive"))
    )
    (net (code "86") (name "Net-(T4-B)") (class "Default")
      (node (ref "R21") (pin "2") (pinfunction "2_2") (pintype "passive"))
      (node (ref "T4") (pin "1") (pinfunction "B_1") (pintype "passive"))
    )
    (net (code "87") (name "Net-(T4-C)") (class "Default")
      (node (ref "R33") (pin "2") (pinfunction "2_2") (pintype "passive"))
      (node (ref "T4") (pin "3") (pinfunction "C_3") (pintype "passive"))
    )
    (net (code "88") (name "Net-(T5-B)") (class "Default")
      (node (ref "R27") (pin "2") (pinfunction "2_2") (pintype "passive"))
      (node (ref "T5") (pin "1") (pinfunction "B_1") (pintype "passive"))
    )
    (net (code "89") (name "Net-(T5-C)") (class "Default")
      (node (ref "R40") (pin "2") (pinfunction "2_2") (pintype "passive"))
      (node (ref "T5") (pin "3") (pinfunction "C_3") (pintype "passive"))
    )
    (net (code "90") (name "Net-(T6-B)") (class "Default")
      (node (ref "R22") (pin "2") (pinfunction "2_2") (pintype "passive"))
      (node (ref "T6") (pin "1") (pinfunction "B_1") (pintype "passive"))
    )
    (net (code "91") (name "Net-(T6-C)") (class "Default")
      (node (ref "R34") (pin "2") (pinfunction "2_2") (pintype "passive"))
      (node (ref "T6") (pin "3") (pinfunction "C_3") (pintype "passive"))
    )
    (net (code "92") (name "Net-(T7-B)") (class "Default")
      (node (ref "R28") (pin "2") (pinfunction "2_2") (pintype "passive"))
      (node (ref "T7") (pin "1") (pinfunction "B_1") (pintype "passive"))
    )
    (net (code "93") (name "Net-(T7-C)") (class "Default")
      (node (ref "R41") (pin "2") (pinfunction "2_2") (pintype "passive"))
      (node (ref "T7") (pin "3") (pinfunction "C_3") (pintype "passive"))
    )
    (net (code "94") (name "Net-(T8-B)") (class "Default")
      (node (ref "R23") (pin "2") (pinfunction "2_2") (pintype "passive"))
      (node (ref "T8") (pin "1") (pinfunction "B_1") (pintype "passive"))
    )
    (net (code "95") (name "Net-(T8-C)") (class "Default")
      (node (ref "R35") (pin "2") (pinfunction "2_2") (pintype "passive"))
      (node (ref "T8") (pin "3") (pinfunction "C_3") (pintype "passive"))
    )
    (net (code "96") (name "Net-(T9-B)") (class "Default")
      (node (ref "R29") (pin "2") (pinfunction "2_2") (pintype "passive"))
      (node (ref "T9") (pin "1") (pinfunction "B_1") (pintype "passive"))
    )
    (net (code "97") (name "Net-(T9-C)") (class "Default")
      (node (ref "R42") (pin "2") (pinfunction "2_2") (pintype "passive"))
      (node (ref "T9") (pin "3") (pinfunction "C_3") (pintype "passive"))
    )
    (net (code "98") (name "Net-(T10-B)") (class "Default")
      (node (ref "R24") (pin "2") (pinfunction "2_2") (pintype "passive"))
      (node (ref "T10") (pin "1") (pinfunction "B_1") (pintype "passive"))
    )
    (net (code "99") (name "Net-(T10-C)") (class "Default")
      (node (ref "R36") (pin "2") (pinfunction "2_2") (pintype "passive"))
      (node (ref "T10") (pin "3") (pinfunction "C_3") (pintype "passive"))
    )
    (net (code "100") (name "Net-(T11-B)") (class "Default")
      (node (ref "R30") (pin "2") (pinfunction "2_2") (pintype "passive"))
      (node (ref "T11") (pin "1") (pinfunction "B_1") (pintype "passive"))
    )
    (net (code "101") (name "Net-(T11-C)") (class "Default")
      (node (ref "R44") (pin "2") (pinfunction "2_2") (pintype "passive"))
      (node (ref "T11") (pin "3") (pinfunction "C_3") (pintype "passive"))
    )
    (net (code "102") (name "Net-(T12-B)") (class "Default")
      (node (ref "R25") (pin "2") (pinfunction "2_2") (pintype "passive"))
      (node (ref "T12") (pin "1") (pinfunction "B_1") (pintype "passive"))
    )
    (net (code "103") (name "Net-(T12-C)") (class "Default")
      (node (ref "R37") (pin "2") (pinfunction "2_2") (pintype "passive"))
      (node (ref "T12") (pin "3") (pinfunction "C_3") (pintype "passive"))
    )
    (net (code "104") (name "Net-(T13-B)") (class "Default")
      (node (ref "R31") (pin "2") (pinfunction "2_2") (pintype "passive"))
      (node (ref "T13") (pin "1") (pinfunction "B_1") (pintype "passive"))
    )
    (net (code "105") (name "Net-(T13-C)") (class "Default")
      (node (ref "R45") (pin "2") (pinfunction "2_2") (pintype "passive"))
      (node (ref "T13") (pin "3") (pinfunction "C_3") (pintype "passive"))
    )
    (net (code "106") (name "Net-(U1-A0)") (class "Default")
      (node (ref "C50") (pin "1") (pinfunction "1_1") (pintype "passive"))
      (node (ref "R48") (pin "2") (pinfunction "2_2") (pintype "passive"))
      (node (ref "U1") (pin "3") (pinfunction "A0_3") (pintype "bidirectional"))
    )
    (net (code "107") (name "Net-(U1-A1)") (class "Default")
      (node (ref "C49") (pin "1") (pinfunction "1_1") (pintype "passive"))
      (node (ref "R49") (pin "2") (pinfunction "2_2") (pintype "passive"))
      (node (ref "U1") (pin "4") (pinfunction "A1_4") (pintype "bidirectional"))
    )
    (net (code "108") (name "Net-(U1-A2)") (class "Default")
      (node (ref "C48") (pin "1") (pinfunction "1_1") (pintype "passive"))
      (node (ref "R50") (pin "2") (pinfunction "2_2") (pintype "passive"))
      (node (ref "U1") (pin "5") (pinfunction "A2_5") (pintype "bidirectional"))
    )
    (net (code "109") (name "Net-(U1-A3)") (class "Default")
      (node (ref "C47") (pin "1") (pinfunction "1_1") (pintype "passive"))
      (node (ref "R51") (pin "2") (pinfunction "2_2") (pintype "passive"))
      (node (ref "U1") (pin "6") (pinfunction "A3_6") (pintype "bidirectional"))
    )
    (net (code "110") (name "Net-(U1-A4)") (class "Default")
      (node (ref "C46") (pin "1") (pinfunction "1_1") (pintype "passive"))
      (node (ref "R52") (pin "2") (pinfunction "2_2") (pintype "passive"))
      (node (ref "U1") (pin "7") (pinfunction "A4_7") (pintype "bidirectional"))
    )
    (net (code "111") (name "Net-(U1-A5)") (class "Default")
      (node (ref "R58") (pin "1") (pinfunction "1_1") (pintype "passive"))
      (node (ref "U1") (pin "8") (pinfunction "A5_8") (pintype "bidirectional"))
    )
    (net (code "112") (name "Net-(U1-A6)") (class "Default")
      (node (ref "R57") (pin "1") (pinfunction "1_1") (pintype "passive"))
      (node (ref "U1") (pin "9") (pinfunction "A6_9") (pintype "bidirectional"))
    )
    (net (code "113") (name "Net-(U1-A7)") (class "Default")
      (node (ref "R56") (pin "1") (pinfunction "1_1") (pintype "passive"))
      (node (ref "U1") (pin "10") (pinfunction "A7_10") (pintype "bidirectional"))
    )
    (net (code "114") (name "Net-(U1-B5)") (class "Default")
      (node (ref "R61") (pin "1") (pinfunction "1_1") (pintype "passive"))
      (node (ref "U1") (pin "16") (pinfunction "B5_16") (pintype "bidirectional"))
    )
    (net (code "115") (name "Net-(U1-B6)") (class "Default")
      (node (ref "R60") (pin "1") (pinfunction "1_1") (pintype "passive"))
      (node (ref "U1") (pin "15") (pinfunction "B6_15") (pintype "bidirectional"))
    )
    (net (code "116") (name "Net-(U1-B7)") (class "Default")
      (node (ref "R59") (pin "1") (pinfunction "1_1") (pintype "passive"))
      (node (ref "U1") (pin "14") (pinfunction "B7_14") (pintype "bidirectional"))
    )
    (net (code "117") (name "Net-(U2-A0)") (class "Default")
      (node (ref "C45") (pin "1") (pinfunction "1_1") (pintype "passive"))
      (node (ref "R4") (pin "2") (pinfunction "2_2") (pintype "passive"))
      (node (ref "U2") (pin "3") (pinfunction "A0_3") (pintype "bidirectional"))
    )
    (net (code "118") (name "Net-(U2-A1)") (class "Default")
      (node (ref "C44") (pin "1") (pinfunction "1_1") (pintype "passive"))
      (node (ref "R5") (pin "2") (pinfunction "2_2") (pintype "passive"))
      (node (ref "U2") (pin "4") (pinfunction "A1_4") (pintype "bidirectional"))
    )
    (net (code "119") (name "Net-(U2-A2)") (class "Default")
      (node (ref "C43") (pin "1") (pinfunction "1_1") (pintype "passive"))
      (node (ref "R6") (pin "2") (pinfunction "2_2") (pintype "passive"))
      (node (ref "U2") (pin "5") (pinfunction "A2_5") (pintype "bidirectional"))
    )
    (net (code "120") (name "Net-(U2-A3)") (class "Default")
      (node (ref "C42") (pin "1") (pinfunction "1_1") (pintype "passive"))
      (node (ref "R7") (pin "2") (pinfunction "2_2") (pintype "passive"))
      (node (ref "U2") (pin "6") (pinfunction "A3_6") (pintype "bidirectional"))
    )
    (net (code "121") (name "Net-(U2-A4)") (class "Default")
      (node (ref "C41") (pin "1") (pinfunction "1_1") (pintype "passive"))
      (node (ref "R8") (pin "2") (pinfunction "2_2") (pintype "passive"))
      (node (ref "U2") (pin "7") (pinfunction "A4_7") (pintype "bidirectional"))
    )
    (net (code "122") (name "Net-(U2-A5)") (class "Default")
      (node (ref "R64") (pin "1") (pinfunction "1_1") (pintype "passive"))
      (node (ref "U2") (pin "8") (pinfunction "A5_8") (pintype "bidirectional"))
    )
    (net (code "123") (name "Net-(U2-A6)") (class "Default")
      (node (ref "R63") (pin "1") (pinfunction "1_1") (pintype "passive"))
      (node (ref "U2") (pin "9") (pinfunction "A6_9") (pintype "bidirectional"))
    )
    (net (code "124") (name "Net-(U2-A7)") (class "Default")
      (node (ref "R62") (pin "1") (pinfunction "1_1") (pintype "passive"))
      (node (ref "U2") (pin "10") (pinfunction "A7_10") (pintype "bidirectional"))
    )
    (net (code "125") (name "Net-(U2-B5)") (class "Default")
      (node (ref "R67") (pin "1") (pinfunction "1_1") (pintype "passive"))
      (node (ref "U2") (pin "16") (pinfunction "B5_16") (pintype "bidirectional"))
    )
    (net (code "126") (name "Net-(U2-B6)") (class "Default")
      (node (ref "R66") (pin "1") (pinfunction "1_1") (pintype "passive"))
      (node (ref "U2") (pin "15") (pinfunction "B6_15") (pintype "bidirectional"))
    )
    (net (code "127") (name "Net-(U2-B7)") (class "Default")
      (node (ref "R65") (pin "1") (pinfunction "1_1") (pintype "passive"))
      (node (ref "U2") (pin "14") (pinfunction "B7_14") (pintype "bidirectional"))
    )
    (net (code "128") (name "Net-(USB-2)") (class "Default")
      (node (ref "IC2") (pin "P$1") (pinfunction "IO1_P$1") (pintype "bidirectional"))
      (node (ref "USB") (pin "P$2") (pinfunction "2_P$2") (pintype "bidirectional"))
    )
    (net (code "129") (name "Net-(USB-3)") (class "Default")
      (node (ref "IC2") (pin "P$3") (pinfunction "IO2_P$3") (pintype "bidirectional"))
      (node (ref "USB") (pin "P$3") (pinfunction "3_P$3") (pintype "bidirectional"))
    )
    (net (code "130") (name "Net-(USB-P$1)") (class "Default")
      (node (ref "R69") (pin "1") (pinfunction "1_1") (pintype "passive"))
      (node (ref "USB") (pin "SHIELD_1") (pinfunction "P$1_SHIELD_1") (pintype "bidirectional"))
    )
    (net (code "131") (name "Net-(USB-P$4)") (class "Default")
      (node (ref "C2") (pin "1") (pinfunction "1_1") (pintype "passive"))
      (node (ref "USB") (pin "SHIELD_4") (pinfunction "P$4_SHIELD_4") (pintype "bidirectional"))
    )
    (net (code "132") (name "unconnected-(IC1-PA0(ADCA0{slash}AREFA)-Pad95)") (class "Default")
      (node (ref "IC1") (pin "95") (pinfunction "PA0(ADCA0/AREFA)_95") (pintype "bidirectional"))
    )
    (net (code "133") (name "unconnected-(IC1-PA1(ADCA1)-Pad96)") (class "Default")
      (node (ref "IC1") (pin "96") (pinfunction "PA1(ADCA1)_96") (pintype "bidirectional"))
    )
    (net (code "134") (name "unconnected-(IC1-PA2(ADCA2)-Pad97)") (class "Default")
      (node (ref "IC1") (pin "97") (pinfunction "PA2(ADCA2)_97") (pintype "bidirectional"))
    )
    (net (code "135") (name "unconnected-(IC1-PA3(ADCA3)-Pad98)") (class "Default")
      (node (ref "IC1") (pin "98") (pinfunction "PA3(ADCA3)_98") (pintype "bidirectional"))
    )
    (net (code "136") (name "unconnected-(IC1-PA4(ADCA4)-Pad99)") (class "Default")
      (node (ref "IC1") (pin "99") (pinfunction "PA4(ADCA4)_99") (pintype "bidirectional"))
    )
    (net (code "137") (name "unconnected-(IC1-PA5(ADCA5)-Pad100)") (class "Default")
      (node (ref "IC1") (pin "100") (pinfunction "PA5(ADCA5)_100") (pintype "bidirectional"))
    )
    (net (code "138") (name "unconnected-(IC1-PA7{slash}(ADCA7{slash}AC0-OUT)-Pad2)") (class "Default")
      (node (ref "IC1") (pin "2") (pinfunction "PA7/(ADCA7/AC0-OUT)_2") (pintype "bidirectional"))
    )
    (net (code "139") (name "unconnected-(IC1-PB0(ADCB0{slash}AREFB)-Pad5)") (class "Default")
      (node (ref "IC1") (pin "5") (pinfunction "PB0(ADCB0/AREFB)_5") (pintype "bidirectional"))
    )
    (net (code "140") (name "unconnected-(IC1-PB1(ADCB1)-Pad6)") (class "Default")
      (node (ref "IC1") (pin "6") (pinfunction "PB1(ADCB1)_6") (pintype "bidirectional"))
    )
    (net (code "141") (name "unconnected-(IC1-PB2(ADCB2{slash}DAC0)-Pad7)") (class "Default")
      (node (ref "IC1") (pin "7") (pinfunction "PB2(ADCB2/DAC0)_7") (pintype "bidirectional"))
    )
    (net (code "142") (name "unconnected-(IC1-PB3(ADCB3{slash}DAC1)-Pad8)") (class "Default")
      (node (ref "IC1") (pin "8") (pinfunction "PB3(ADCB3/DAC1)_8") (pintype "bidirectional"))
    )
    (net (code "143") (name "unconnected-(IC1-PB4(ADCB4{slash}TMS)-Pad9)") (class "Default")
      (node (ref "IC1") (pin "9") (pinfunction "PB4(ADCB4/TMS)_9") (pintype "bidirectional"))
    )
    (net (code "144") (name "unconnected-(IC1-PB7(ADCB7{slash}AC0-OUT{slash}TDO)-Pad12)") (class "Default")
      (node (ref "IC1") (pin "12") (pinfunction "PB7(ADCB7/AC0-OUT/TDO)_12") (pintype "bidirectional"))
    )
    (net (code "145") (name "unconnected-(IC1-PC4(OC1A{slash}~{SS})-Pad19)") (class "Default")
      (node (ref "IC1") (pin "19") (pinfunction "PC4(OC1A/~{SS})_19") (pintype "bidirectional"))
    )
    (net (code "146") (name "unconnected-(IC1-PC5(OC1B{slash}MOSI{slash}XCK1)-Pad20)") (class "Default")
      (node (ref "IC1") (pin "20") (pinfunction "PC5(OC1B/MOSI/XCK1)_20") (pintype "bidirectional"))
    )
    (net (code "147") (name "unconnected-(IC1-PD5(OC1B{slash}XCK1{slash}MOSI)-Pad30)") (class "Default")
      (node (ref "IC1") (pin "30") (pinfunction "PD5(OC1B/XCK1/MOSI)_30") (pintype "bidirectional"))
    )
    (net (code "148") (name "unconnected-(IC1-PE1(OC0B{slash}XCK0{slash}SCL)-Pad36)") (class "Default")
      (node (ref "IC1") (pin "36") (pinfunction "PE1(OC0B/XCK0/SCL)_36") (pintype "bidirectional"))
    )
    (net (code "149") (name "unconnected-(IC1-PE6(RSC1{slash}MISO{slash}TOSC2)-Pad41)") (class "Default")
      (node (ref "IC1") (pin "41") (pinfunction "PE6(RSC1/MISO/TOSC2)_41") (pintype "bidirectional"))
    )
    (net (code "150") (name "unconnected-(IC1-PE7(TSD1{slash}SCK{slash}CLKO{slash}EVO{slash}TOSC1)-Pad42)") (class "Default")
      (node (ref "IC1") (pin "42") (pinfunction "PE7(TSD1/SCK/CLKO/EVO/TOSC1)_42") (pintype "bidirectional"))
    )
    (net (code "151") (name "unconnected-(IC1-PF0(OC0A{slash}SDA)-Pad45)") (class "Default")
      (node (ref "IC1") (pin "45") (pinfunction "PF0(OC0A/SDA)_45") (pintype "bidirectional"))
    )
    (net (code "152") (name "unconnected-(IC1-PF1(OC0B{slash}XCK0{slash}SCL)-Pad46)") (class "Default")
      (node (ref "IC1") (pin "46") (pinfunction "PF1(OC0B/XCK0/SCL)_46") (pintype "bidirectional"))
    )
    (net (code "153") (name "unconnected-(IC1-PF4(OC1A{slash}~{SS})-Pad49)") (class "Default")
      (node (ref "IC1") (pin "49") (pinfunction "PF4(OC1A/~{SS})_49") (pintype "bidirectional"))
    )
    (net (code "154") (name "unconnected-(IC1-PF5(OC1B{slash}XCK1{slash}MOSI)-Pad50)") (class "Default")
      (node (ref "IC1") (pin "50") (pinfunction "PF5(OC1B/XCK1/MOSI)_50") (pintype "bidirectional"))
    )
    (net (code "155") (name "unconnected-(IC1-PF7(TXD1{slash}SCK)-Pad52)") (class "Default")
      (node (ref "IC1") (pin "52") (pinfunction "PF7(TXD1/SCK)_52") (pintype "bidirectional"))
    )
    (net (code "156") (name "unconnected-(IC1-PJ3(D3{slash}A3{slash}A11)-Pad68)") (class "Default")
      (node (ref "IC1") (pin "68") (pinfunction "PJ3(D3/A3/A11)_68") (pintype "bidirectional"))
    )
    (net (code "157") (name "unconnected-(IC1-PJ4(A8{slash}D4{slash}A4{slash}A12)-Pad69)") (class "Default")
      (node (ref "IC1") (pin "69") (pinfunction "PJ4(A8/D4/A4/A12)_69") (pintype "bidirectional"))
    )
    (net (code "158") (name "unconnected-(IC1-PJ5(A9{slash}D5{slash}A5{slash}A13)-Pad70)") (class "Default")
      (node (ref "IC1") (pin "70") (pinfunction "PJ5(A9/D5/A5/A13)_70") (pintype "bidirectional"))
    )
    (net (code "159") (name "unconnected-(IC1-PJ7(A11{slash}D7{slash}A7{slash}A15)-Pad72)") (class "Default")
      (node (ref "IC1") (pin "72") (pinfunction "PJ7(A11/D7/A7/A15)_72") (pintype "bidirectional"))
    )
    (net (code "160") (name "unconnected-(IC1-PK3(A3{slash}A11{slash}A19)-Pad78)") (class "Default")
      (node (ref "IC1") (pin "78") (pinfunction "PK3(A3/A11/A19)_78") (pintype "bidirectional"))
    )
    (net (code "161") (name "unconnected-(IC1-PK4(A4{slash}A12{slash}A20)-Pad79)") (class "Default")
      (node (ref "IC1") (pin "79") (pinfunction "PK4(A4/A12/A20)_79") (pintype "bidirectional"))
    )
    (net (code "162") (name "unconnected-(IC1-PK5(A5{slash}A13{slash}A22)-Pad80)") (class "Default")
      (node (ref "IC1") (pin "80") (pinfunction "PK5(A5/A13/A22)_80") (pintype "bidirectional"))
    )
    (net (code "163") (name "unconnected-(IC1-PK6(A6{slash}A14{slash}A22)-Pad81)") (class "Default")
      (node (ref "IC1") (pin "81") (pinfunction "PK6(A6/A14/A22)_81") (pintype "bidirectional"))
    )
    (net (code "164") (name "unconnected-(IC1-PK7(A7{slash}A15{slash}A23)-Pad82)") (class "Default")
      (node (ref "IC1") (pin "82") (pinfunction "PK7(A7/A15/A23)_82") (pintype "bidirectional"))
    )
    (net (code "165") (name "unconnected-(IC1-PQ0(TOSC1)-Pad85)") (class "Default")
      (node (ref "IC1") (pin "85") (pinfunction "PQ0(TOSC1)_85") (pintype "bidirectional"))
    )
    (net (code "166") (name "unconnected-(IC1-PQ1(TOSC2)-Pad86)") (class "Default")
      (node (ref "IC1") (pin "86") (pinfunction "PQ1(TOSC2)_86") (pintype "bidirectional"))
    )
    (net (code "167") (name "unconnected-(IC1-PQ2-Pad87)") (class "Default")
      (node (ref "IC1") (pin "87") (pinfunction "PQ2_87") (pintype "bidirectional"))
    )
    (net (code "168") (name "unconnected-(IC1-PQ3-Pad88)") (class "Default")
      (node (ref "IC1") (pin "88") (pinfunction "PQ3_88") (pintype "bidirectional"))
    )
    (net (code "169") (name "unconnected-(IC1-PR0(XTAL2)-Pad91)") (class "Default")
      (node (ref "IC1") (pin "91") (pinfunction "PR0(XTAL2)_91") (pintype "bidirectional"))
    )
    (net (code "170") (name "unconnected-(IC3-CBUS0-Pad23)") (class "Default")
      (node (ref "IC3") (pin "23") (pinfunction "CBUS0_23") (pintype "bidirectional"))
    )
    (net (code "171") (name "unconnected-(IC3-CBUS1-Pad22)") (class "Default")
      (node (ref "IC3") (pin "22") (pinfunction "CBUS1_22") (pintype "bidirectional"))
    )
    (net (code "172") (name "unconnected-(IC3-CBUS2-Pad13)") (class "Default")
      (node (ref "IC3") (pin "13") (pinfunction "CBUS2_13") (pintype "bidirectional"))
    )
    (net (code "173") (name "unconnected-(IC3-CBUS3-Pad14)") (class "Default")
      (node (ref "IC3") (pin "14") (pinfunction "CBUS3_14") (pintype "bidirectional"))
    )
    (net (code "174") (name "unconnected-(IC3-CBUS4-Pad12)") (class "Default")
      (node (ref "IC3") (pin "12") (pinfunction "CBUS4_12") (pintype "bidirectional"))
    )
    (net (code "175") (name "unconnected-(IC3-OSCI-Pad27)") (class "Default")
      (node (ref "IC3") (pin "27") (pinfunction "OSCI_27") (pintype "input"))
    )
    (net (code "176") (name "unconnected-(IC3-OSCO-Pad28)") (class "Default")
      (node (ref "IC3") (pin "28") (pinfunction "OSCO_28") (pintype "output"))
    )
    (net (code "177") (name "unconnected-(IC3-~{DCD}-Pad10)") (class "Default")
      (node (ref "IC3") (pin "10") (pinfunction "~{DCD}_10") (pintype "input"))
    )
    (net (code "178") (name "unconnected-(IC3-~{DSR}-Pad9)") (class "Default")
      (node (ref "IC3") (pin "9") (pinfunction "~{DSR}_9") (pintype "input"))
    )
    (net (code "179") (name "unconnected-(IC3-~{DTR}-Pad2)") (class "Default")
      (node (ref "IC3") (pin "2") (pinfunction "~{DTR}_2") (pintype "output"))
    )
    (net (code "180") (name "unconnected-(IC3-~{RESET}-Pad19)") (class "Default")
      (node (ref "IC3") (pin "19") (pinfunction "~{RESET}_19") (pintype "input"))
    )
    (net (code "181") (name "unconnected-(IC3-~{RI}-Pad6)") (class "Default")
      (node (ref "IC3") (pin "6") (pinfunction "~{RI}_6") (pintype "input"))
    )
    (net (code "182") (name "unconnected-(IC4-N{slash}C-Pad4)") (class "Default")
      (node (ref "IC4") (pin "4") (pinfunction "N/C_4") (pintype "bidirectional"))
    )
    (net (code "183") (name "unconnected-(IC5-N{slash}C-Pad4)") (class "Default")
      (node (ref "IC5") (pin "4") (pinfunction "N/C_4") (pintype "bidirectional"))
    )
    (net (code "184") (name "unconnected-(IC6-AVDD{slash}NC-Pad3)") (class "Default")
      (node (ref "IC6") (pin "3") (pinfunction "AVDD/NC_3") (pintype "bidirectional"))
    )
    (net (code "185") (name "unconnected-(IC6-BGND{slash}NC-Pad7)") (class "Default")
      (node (ref "IC6") (pin "7") (pinfunction "BGND/NC_7") (pintype "bidirectional"))
    )
    (net (code "186") (name "unconnected-(OSC-STANDBY#-PadP$1)") (class "Default")
      (node (ref "OSC") (pin "P$1") (pinfunction "STANDBY#_P$1") (pintype "passive"))
    )
    (net (code "187") (name "unconnected-(PDI-Pad3)") (class "Default")
      (node (ref "PDI") (pin "3") (pinfunction "3_3") (pintype "passive"))
    )
    (net (code "188") (name "unconnected-(PDI-Pad4)") (class "Default")
      (node (ref "PDI") (pin "4") (pinfunction "4_4") (pintype "passive"))
    )
    (net (code "189") (name "unconnected-(SV1-Pad8)") (class "Default")
      (node (ref "SV1") (pin "8") (pinfunction "8_8") (pintype "passive"))
    )
    (net (code "190") (name "unconnected-(USB-4-PadP$4)") (class "Default")
      (node (ref "USB") (pin "P$4") (pinfunction "4_P$4") (pintype "bidirectional"))
    )
    (net (code "191") (name "unconnected-(USB-P$2-PadSHIELD_2)") (class "Default")
      (node (ref "USB") (pin "SHIELD_2") (pinfunction "P$2_SHIELD_2") (pintype "bidirectional"))
    )
    (net (code "192") (name "unconnected-(USB-P$3-PadSHIELD_3)") (class "Default")
      (node (ref "USB") (pin "SHIELD_3") (pinfunction "P$3_SHIELD_3") (pintype "bidirectional"))
    )
  )
)
